# Control_HAT_v0_2B.net
KiCad netlist of a schematic drawn in EAGLE
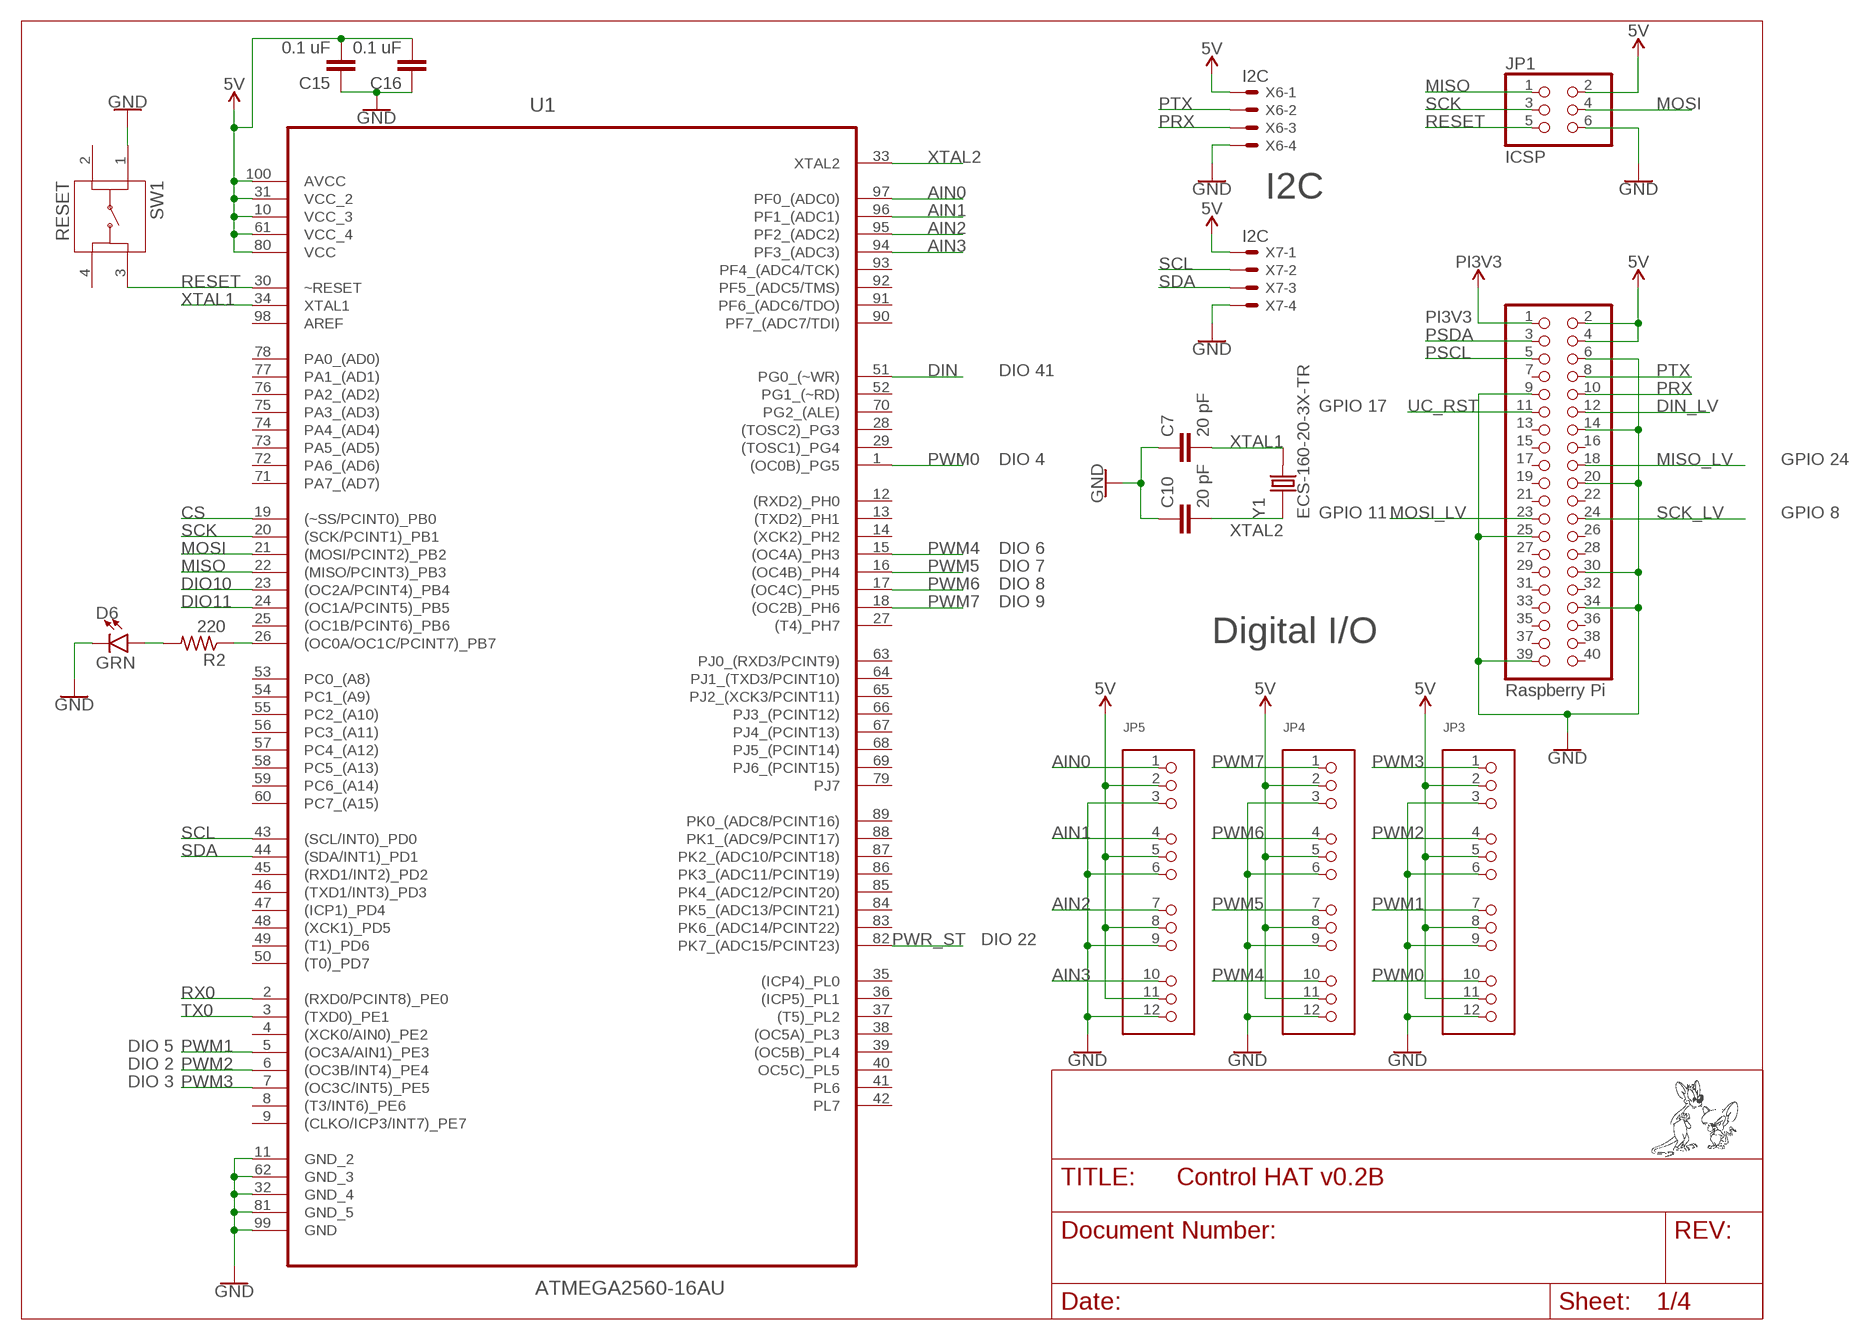
[diagram p0: schematic, sheet 1]
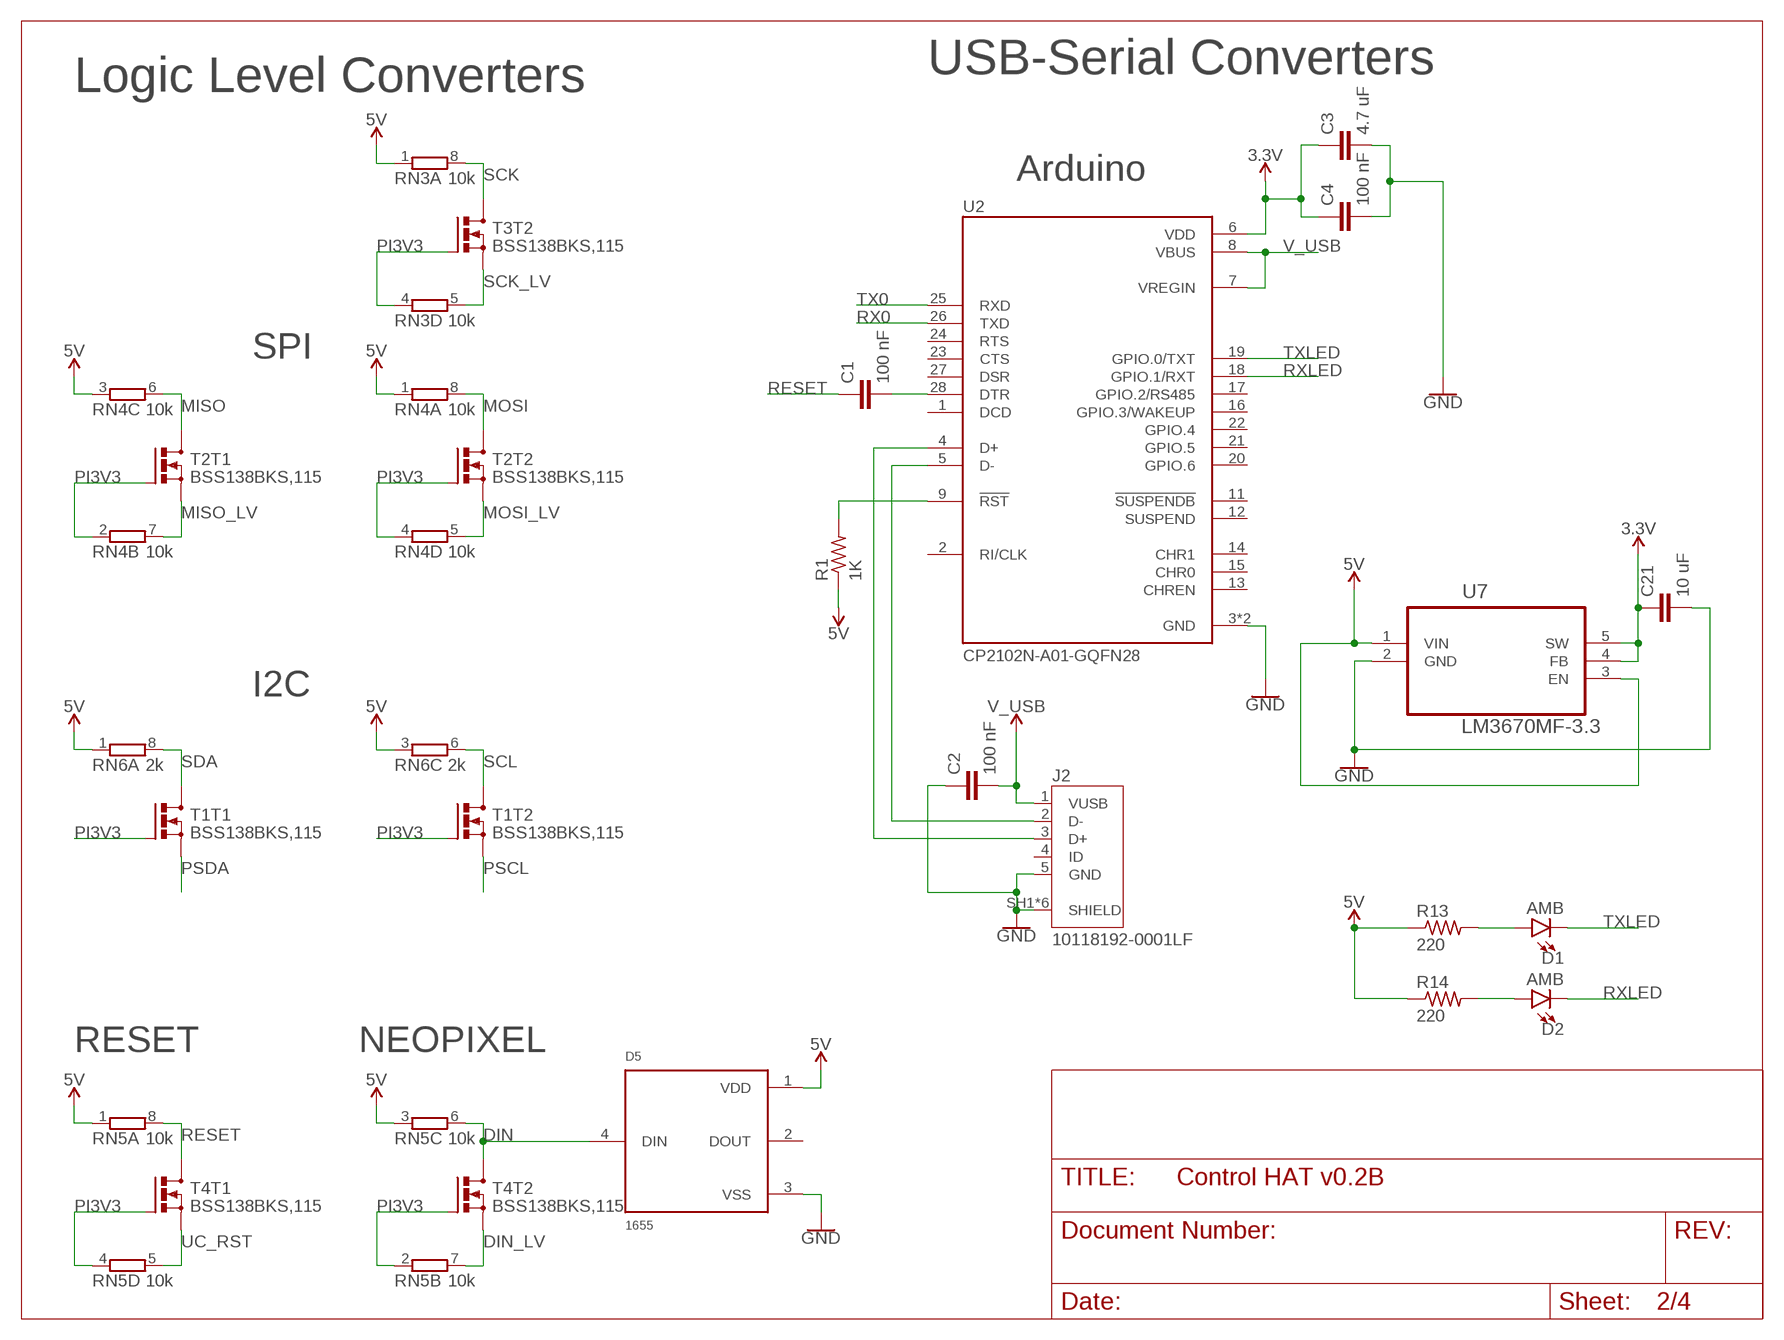
[diagram p1: schematic, sheet 2]
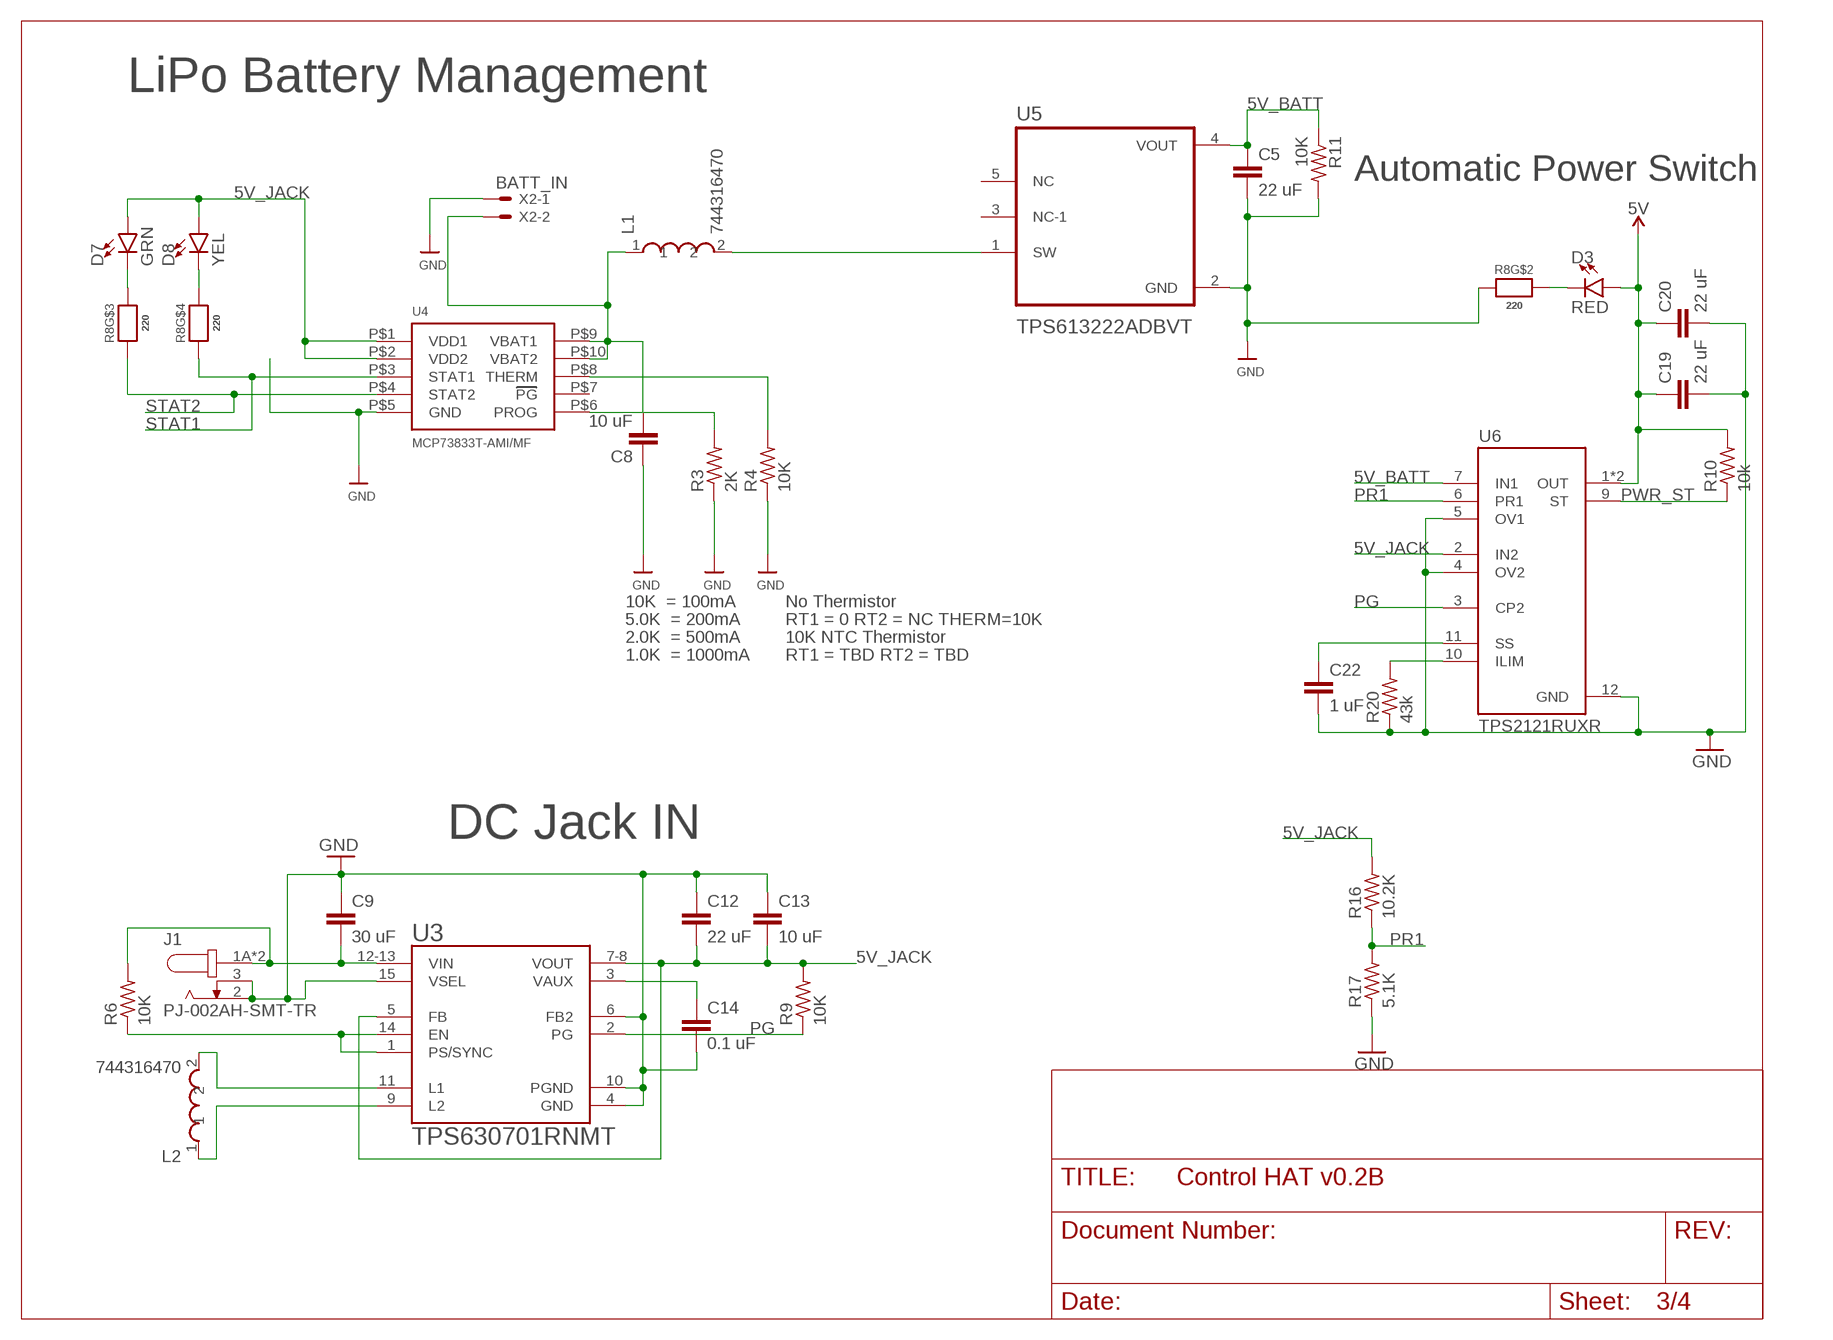
[diagram p2: schematic, sheet 3]
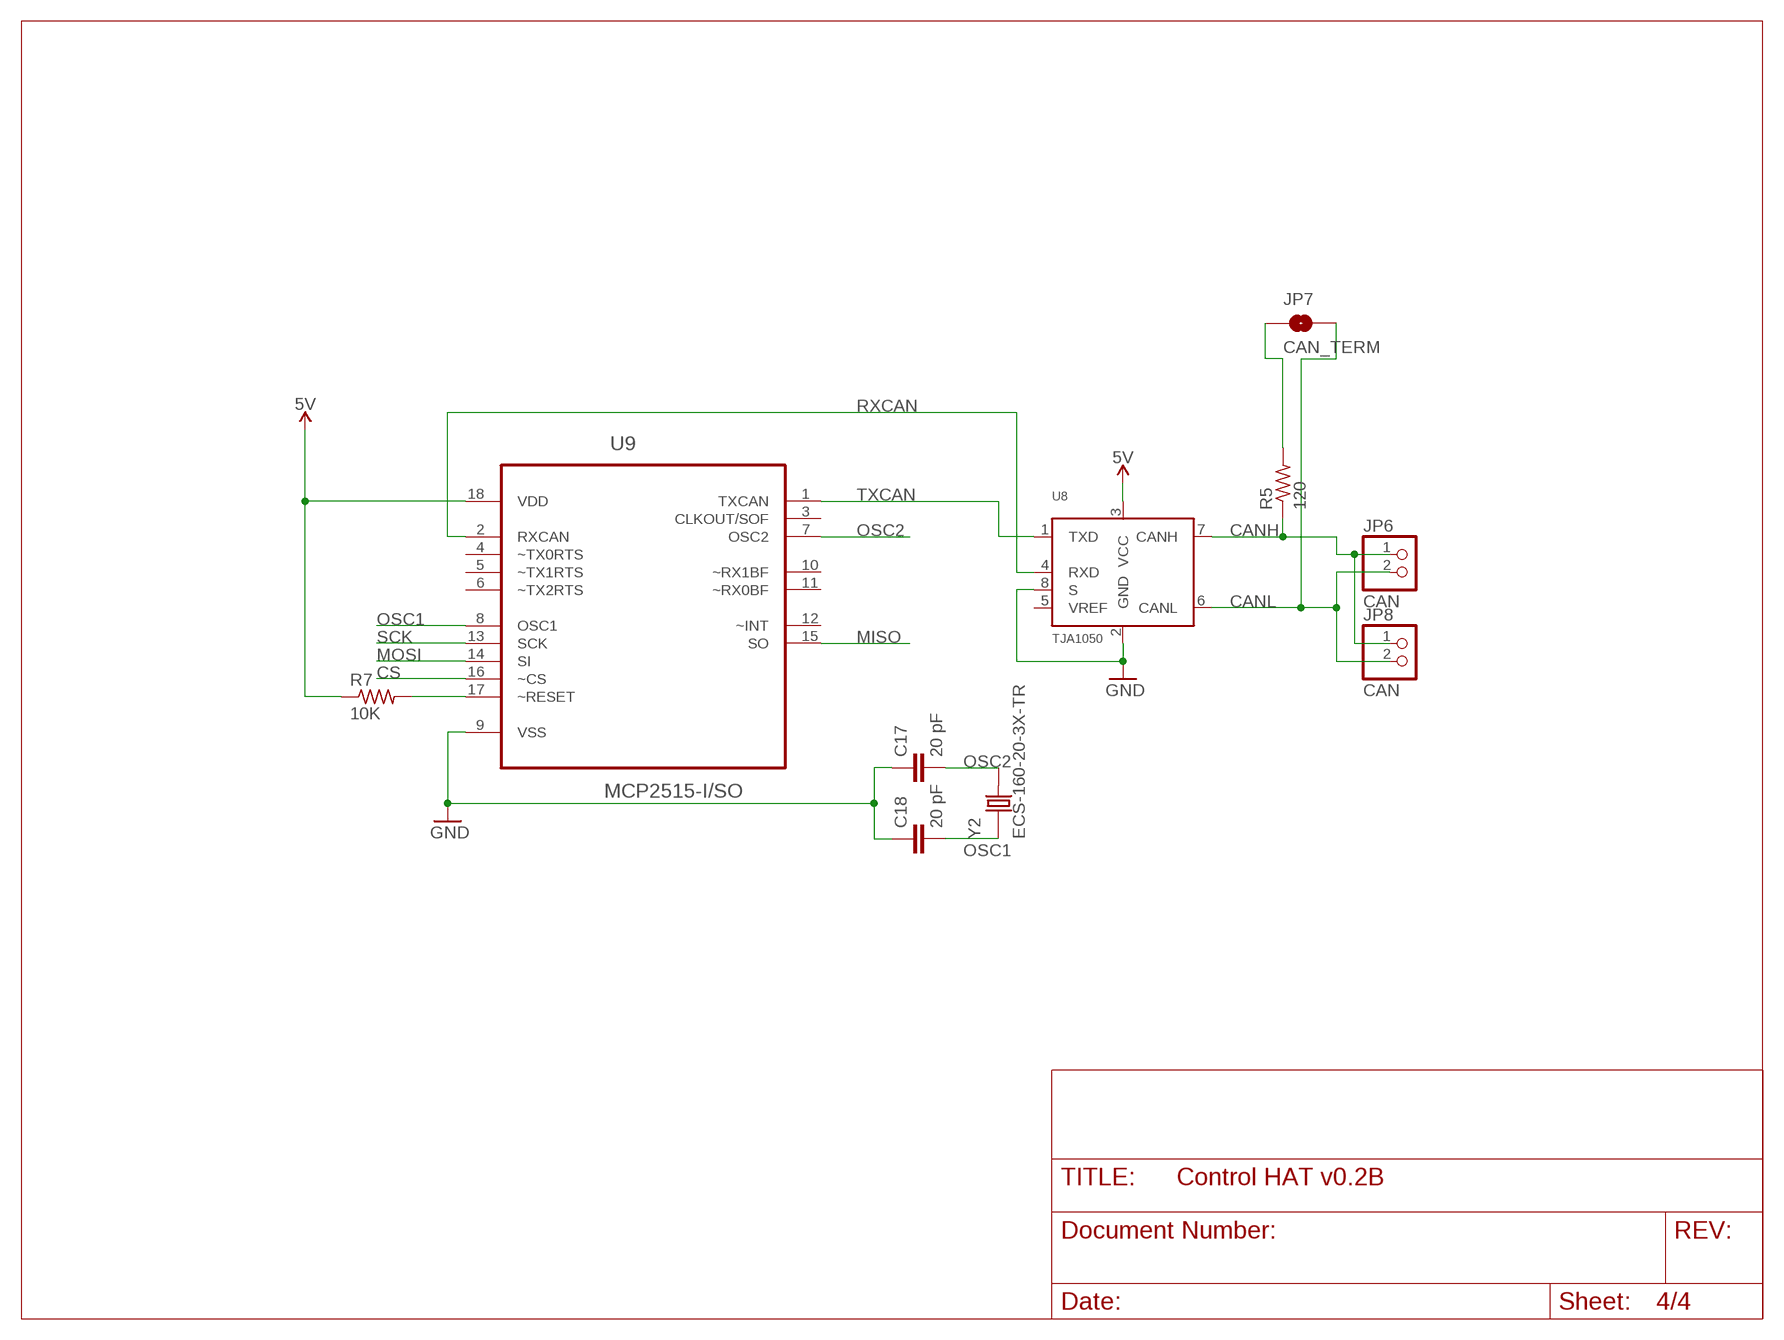
[diagram p3: schematic, sheet 4]

(export (version "E")
  (design (tool "Eeschema 10.0.6"))
  (components
    (comp (ref "C1")
      (value "100 nF")
      (footprint "eagle-import:C0603")
      (libsource (lib "eagle-import") (part "C-EUC0603"))
    )
    (comp (ref "C2")
      (value "100 nF")
      (footprint "eagle-import:C0603")
      (libsource (lib "eagle-import") (part "C-EUC0603"))
    )
    (comp (ref "C3")
      (value "4.7 uF")
      (footprint "eagle-import:C0603")
      (libsource (lib "eagle-import") (part "C-EUC0603"))
    )
    (comp (ref "C4")
      (value "100 nF")
      (footprint "eagle-import:C0603")
      (libsource (lib "eagle-import") (part "C-EUC0603"))
    )
    (comp (ref "C21")
      (value "10 uF")
      (footprint "eagle-import:C0603")
      (libsource (lib "eagle-import") (part "C-EUC0603"))
    )
    (comp (ref "D1")
      (value "AMB")
      (footprint "eagle-import:LED-0603")
      (libsource (lib "eagle-import") (part "LED0603"))
    )
    (comp (ref "D2")
      (value "AMB")
      (footprint "eagle-import:LED-0603")
      (libsource (lib "eagle-import") (part "LED0603"))
    )
    (comp (ref "D5")
      (value "1655")
      (footprint "eagle-import:FCI_1655")
      (fields (field (name "MF") "Adafruit Industries"))
      (libsource (lib "eagle-import") (part "1655"))
    )
    (comp (ref "J2")
      (value "10118192-0001LF")
      (footprint "eagle-import:AMPHENOL_10118192-0001LF")
      (fields (field (name "MF") "Amphenol ICC"))
      (libsource (lib "eagle-import") (part "10118192-0001LF"))
    )
    (comp (ref "R1")
      (value "1K")
      (footprint "eagle-import:R0603")
      (libsource (lib "eagle-import") (part "R-US_R0603"))
    )
    (comp (ref "R13")
      (value "220")
      (footprint "eagle-import:R0603")
      (libsource (lib "eagle-import") (part "R-US_R0603"))
    )
    (comp (ref "R14")
      (value "220")
      (footprint "eagle-import:R0603")
      (libsource (lib "eagle-import") (part "R-US_R0603"))
    )
    (comp (ref "RN3")
      (value "10k")
      (footprint "eagle-import:EXB28V")
      (libsource (lib "eagle-import") (part "4R-NEXB28V"))
    )
    (comp (ref "RN4")
      (value "10k")
      (footprint "eagle-import:EXB28V")
      (libsource (lib "eagle-import") (part "4R-NEXB28V"))
    )
    (comp (ref "RN5")
      (value "10k")
      (footprint "eagle-import:EXB28V")
      (libsource (lib "eagle-import") (part "4R-NEXB28V"))
    )
    (comp (ref "RN6")
      (value "2k")
      (footprint "eagle-import:EXB28V")
      (libsource (lib "eagle-import") (part "4R-NEXB28V"))
    )
    (comp (ref "T1")
      (value "BSS138BKS,115")
      (footprint "eagle-import:SOT363")
      (fields (field (name "MF") "Nexperia USA"))
      (libsource (lib "eagle-import") (part "BSS138BKS,115"))
    )
    (comp (ref "T2")
      (value "BSS138BKS,115")
      (footprint "eagle-import:SOT363")
      (fields (field (name "MF") "Nexperia USA"))
      (libsource (lib "eagle-import") (part "BSS138BKS,115"))
    )
    (comp (ref "T3")
      (value "BSS138BKS,115")
      (footprint "eagle-import:SOT363")
      (fields (field (name "MF") "Nexperia USA"))
      (libsource (lib "eagle-import") (part "BSS138BKS,115"))
    )
    (comp (ref "T4")
      (value "BSS138BKS,115")
      (footprint "eagle-import:SOT363")
      (fields (field (name "MF") "Nexperia USA"))
      (libsource (lib "eagle-import") (part "BSS138BKS,115"))
    )
    (comp (ref "U2")
      (value "CP2102N-A01-GQFN28")
      (footprint "eagle-import:QFN50P500X500X80-29N")
      (fields (field (name "MF") "Silicon Labs"))
      (libsource (lib "eagle-import") (part "CP2102N-A01-GQFN28"))
    )
    (comp (ref "U7")
      (value "LM3670MF-3.3")
      (footprint "eagle-import:SOT95P284X122-5N")
      (fields (field (name "MF") "Texas Instruments") (field (name "MP") "LM3670MF-3.3/NOPB"))
      (libsource (lib "eagle-import") (part "LM3670MF-3.3"))
    )
    (comp (ref "C7")
      (value "20 pF")
      (footprint "eagle-import:C0603")
      (libsource (lib "eagle-import") (part "C-EUC0603"))
    )
    (comp (ref "C10")
      (value "20 pF")
      (footprint "eagle-import:C0603")
      (libsource (lib "eagle-import") (part "C-EUC0603"))
    )
    (comp (ref "C15")
      (value "0.1 uF")
      (footprint "eagle-import:C0603")
      (libsource (lib "eagle-import") (part "C-EUC0603"))
    )
    (comp (ref "C16")
      (value "0.1 uF")
      (footprint "eagle-import:C0603")
      (libsource (lib "eagle-import") (part "C-EUC0603"))
    )
    (comp (ref "D6")
      (value "GRN")
      (footprint "eagle-import:LED-0603")
      (libsource (lib "eagle-import") (part "LED0603"))
    )
    (comp (ref "JP1")
      (value "ICSP")
      (footprint "eagle-import:2X03")
      (libsource (lib "eagle-import") (part "PINHD-2X3"))
    )
    (comp (ref "JP2")
      (value "Raspberry Pi")
      (footprint "eagle-import:2X20")
      (libsource (lib "eagle-import") (part "PINHD-2X20"))
    )
    (comp (ref "JP3")
      (value "HEADER-3X04")
      (footprint "eagle-import:3X04")
      (libsource (lib "eagle-import") (part "HEADER-3X04"))
    )
    (comp (ref "JP4")
      (value "HEADER-3X04")
      (footprint "eagle-import:3X04")
      (libsource (lib "eagle-import") (part "HEADER-3X04"))
    )
    (comp (ref "JP5")
      (value "HEADER-3X04")
      (footprint "eagle-import:3X04")
      (libsource (lib "eagle-import") (part "HEADER-3X04"))
    )
    (comp (ref "R2")
      (value "220")
      (footprint "eagle-import:R0603")
      (libsource (lib "eagle-import") (part "R-US_R0603"))
    )
    (comp (ref "SW1")
      (value "RESET")
      (footprint "eagle-import:SW_1825910-6-4")
      (fields (field (name "COMMENT") "1825910-6") (field (name "MF") "TE Connectivity"))
      (libsource (lib "eagle-import") (part "1825910-6"))
    )
    (comp (ref "U1")
      (value "ATMEGA2560-16AU")
      (footprint "eagle-import:QFP50P1600X1600X120-100N")
      (fields (field (name "MF") "Microchip"))
      (libsource (lib "eagle-import") (part "ATMEGA2560-16AU"))
    )
    (comp (ref "X6")
      (value "I2C")
      (footprint "eagle-import:JST-XH-04-PACKAGE-LONG-PAD")
      (libsource (lib "eagle-import") (part "JST-XH-04-PIN-LONG-PAD"))
    )
    (comp (ref "X7")
      (value "I2C")
      (footprint "eagle-import:JST-XH-04-PACKAGE-LONG-PAD")
      (libsource (lib "eagle-import") (part "JST-XH-04-PIN-LONG-PAD"))
    )
    (comp (ref "Y1")
      (value "ECS-160-20-3X-TR")
      (footprint "eagle-import:XTAL_ECS-160-20-3X-TR")
      (fields (field (name "MF") "ECS Inc."))
      (libsource (lib "eagle-import") (part "ECS-160-20-3X-TR"))
    )
    (comp (ref "C5")
      (value "22 uF")
      (footprint "eagle-import:C0603")
      (libsource (lib "eagle-import") (part "C-EUC0603"))
    )
    (comp (ref "C8")
      (value "10 uF")
      (footprint "eagle-import:C0603")
      (libsource (lib "eagle-import") (part "C-EUC0603"))
    )
    (comp (ref "C9")
      (value "30 uF")
      (footprint "eagle-import:C0603")
      (libsource (lib "eagle-import") (part "C-EUC0603"))
    )
    (comp (ref "C12")
      (value "22 uF")
      (footprint "eagle-import:C0603")
      (libsource (lib "eagle-import") (part "C-EUC0603"))
    )
    (comp (ref "C13")
      (value "10 uF")
      (footprint "eagle-import:C0603")
      (libsource (lib "eagle-import") (part "C-EUC0603"))
    )
    (comp (ref "C14")
      (value "0.1 uF")
      (footprint "eagle-import:C0603")
      (libsource (lib "eagle-import") (part "C-EUC0603"))
    )
    (comp (ref "C19")
      (value "22 uF")
      (footprint "eagle-import:C0603")
      (libsource (lib "eagle-import") (part "C-EUC0603"))
    )
    (comp (ref "C20")
      (value "22 uF")
      (footprint "eagle-import:C0603")
      (libsource (lib "eagle-import") (part "C-EUC0603"))
    )
    (comp (ref "C22")
      (value "1 uF")
      (footprint "eagle-import:C0603")
      (libsource (lib "eagle-import") (part "C-EUC0603"))
    )
    (comp (ref "D3")
      (value "RED")
      (footprint "eagle-import:LED-0603")
      (libsource (lib "eagle-import") (part "LED0603"))
    )
    (comp (ref "D7")
      (value "GRN")
      (footprint "eagle-import:LED-0603")
      (libsource (lib "eagle-import") (part "LED0603"))
    )
    (comp (ref "D8")
      (value "YEL")
      (footprint "eagle-import:LED-0603")
      (libsource (lib "eagle-import") (part "LED0603"))
    )
    (comp (ref "J1")
      (value "PJ-002AH-SMT-TR")
      (footprint "eagle-import:CUI_PJ-002AH-SMT-TR")
      (fields (field (name "DIGI-KEY_PART_NUMBER") "CP-002AHPJCT-ND") (field (name "MF") "CUI Inc."))
      (libsource (lib "eagle-import") (part "PJ-002AH-SMT-TR"))
    )
    (comp (ref "L1")
      (value "744316470")
      (footprint "eagle-import:INDC2220X16")
      (fields (field (name "MF") "Wurth Electronics"))
      (libsource (lib "eagle-import") (part "744316470"))
    )
    (comp (ref "L2")
      (value "744316470")
      (footprint "eagle-import:INDC2220X16")
      (fields (field (name "MF") "Wurth Electronics"))
      (libsource (lib "eagle-import") (part "744316470"))
    )
    (comp (ref "R3")
      (value "2K")
      (footprint "eagle-import:R0603")
      (libsource (lib "eagle-import") (part "R-US_R0603"))
    )
    (comp (ref "R4")
      (value "10K")
      (footprint "eagle-import:R0603")
      (libsource (lib "eagle-import") (part "R-US_R0603"))
    )
    (comp (ref "R6")
      (value "10K")
      (footprint "eagle-import:R0603")
      (libsource (lib "eagle-import") (part "R-US_R0603"))
    )
    (comp (ref "R8")
      (value "220")
      (footprint "eagle-import:RESPACK_4X0603")
      (libsource (lib "eagle-import") (part "RESISTOR_4PACK"))
    )
    (comp (ref "R9")
      (value "10K")
      (footprint "eagle-import:R0603")
      (libsource (lib "eagle-import") (part "R-US_R0603"))
    )
    (comp (ref "R10")
      (value "10k")
      (footprint "eagle-import:R0603")
      (libsource (lib "eagle-import") (part "R-US_R0603"))
    )
    (comp (ref "R11")
      (value "10K")
      (footprint "eagle-import:R0603")
      (libsource (lib "eagle-import") (part "R-US_R0603"))
    )
    (comp (ref "R16")
      (value "10.2K")
      (footprint "eagle-import:R0603")
      (libsource (lib "eagle-import") (part "R-US_R0603"))
    )
    (comp (ref "R17")
      (value "5.1K")
      (footprint "eagle-import:R0603")
      (libsource (lib "eagle-import") (part "R-US_R0603"))
    )
    (comp (ref "R20")
      (value "43k")
      (footprint "eagle-import:R0603")
      (libsource (lib "eagle-import") (part "R-US_R0603"))
    )
    (comp (ref "U3")
      (value "TPS630701RNMT")
      (footprint "eagle-import:QFN50P250X300X100-15N")
      (fields (field (name "MF") "Texas Instruments") (field (name "MP") "TPS63070RNMT"))
      (libsource (lib "eagle-import") (part "TPS63070RNMT"))
    )
    (comp (ref "U4")
      (value "MCP73833T-AMI/MF")
      (footprint "eagle-import:DFN10_3X3MM")
      (libsource (lib "eagle-import") (part "MCP73833DFN"))
    )
    (comp (ref "U5")
      (value "TPS613222ADBVT")
      (footprint "eagle-import:SOT95P280X145-5N")
      (fields (field (name "MF") "Texas Instruments"))
      (libsource (lib "eagle-import") (part "TPS613222ADBVT"))
    )
    (comp (ref "U6")
      (value "TPS2121RUXR")
      (footprint "eagle-import:IC_TPS2121RUXR")
      (fields (field (name "MF") "Texas Instruments"))
      (libsource (lib "eagle-import") (part "TPS2121RUXR"))
    )
    (comp (ref "X2")
      (value "BATT_IN")
      (footprint "eagle-import:JST-XH-02-PACKAGE-LONG-PAD")
      (libsource (lib "eagle-import") (part "JST-XH-02-PIN-LONG-PAD"))
    )
    (comp (ref "C17")
      (value "20 pF")
      (footprint "eagle-import:C0603")
      (libsource (lib "eagle-import") (part "C-EUC0603"))
    )
    (comp (ref "C18")
      (value "20 pF")
      (footprint "eagle-import:C0603")
      (libsource (lib "eagle-import") (part "C-EUC0603"))
    )
    (comp (ref "JP6")
      (value "CAN")
      (footprint "eagle-import:1X02")
      (libsource (lib "eagle-import") (part "PINHD-1X2"))
    )
    (comp (ref "JP7")
      (value "CAN_TERM")
      (footprint "eagle-import:SMT-JUMPER_2_NO_NO-SILK")
      (libsource (lib "eagle-import") (part "JUMPER-SMT_2_NO_NO-SILK"))
    )
    (comp (ref "JP8")
      (value "CAN")
      (footprint "eagle-import:1X02")
      (libsource (lib "eagle-import") (part "PINHD-1X2"))
    )
    (comp (ref "R5")
      (value "120")
      (footprint "eagle-import:R0603")
      (libsource (lib "eagle-import") (part "R-US_R0603"))
    )
    (comp (ref "R7")
      (value "10K")
      (footprint "eagle-import:R0603")
      (libsource (lib "eagle-import") (part "R-US_R0603"))
    )
    (comp (ref "U8")
      (value "TJA1050")
      (footprint "eagle-import:SOT96-1")
      (fields (field (name "DIGI-KEY_PART_NUMBER") "568-10292-1-ND") (field (name "MF") "NXP USA"))
      (libsource (lib "eagle-import") (part "TJA1050"))
    )
    (comp (ref "U9")
      (value "MCP2515-I/SO")
      (footprint "eagle-import:SOIC127P1034X264-18N")
      (fields (field (name "DIGI-KEY_PART_NUMBER") "MCP2515-I/SO-ND") (field (name "MF") "Microchip"))
      (libsource (lib "eagle-import") (part "MCP2515-I/SO"))
    )
    (comp (ref "Y2")
      (value "ECS-160-20-3X-TR")
      (footprint "eagle-import:XTAL_ECS-160-20-3X-TR")
      (fields (field (name "MF") "ECS Inc."))
      (libsource (lib "eagle-import") (part "ECS-160-20-3X-TR"))
    )
  )
  (nets
    (net (code "1") (name "3.3V") (class "Default")
      (node (ref "C21") (pin "1") (pinfunction "1_1") (pintype "passive"))
      (node (ref "C3") (pin "1") (pinfunction "1_1") (pintype "passive"))
      (node (ref "C4") (pin "1") (pinfunction "1_1") (pintype "passive"))
      (node (ref "U2") (pin "6") (pinfunction "VDD_6") (pintype "power_in"))
      (node (ref "U7") (pin "4") (pinfunction "FB_4") (pintype "passive"))
      (node (ref "U7") (pin "5") (pinfunction "SW_5") (pintype "output"))
    )
    (net (code "2") (name "5V") (class "Default")
      (node (ref "C15") (pin "2") (pinfunction "2_2") (pintype "passive"))
      (node (ref "C16") (pin "2") (pinfunction "2_2") (pintype "passive"))
      (node (ref "C19") (pin "1") (pinfunction "1_1") (pintype "passive"))
      (node (ref "C20") (pin "1") (pinfunction "1_1") (pintype "passive"))
      (node (ref "D3") (pin "A") (pinfunction "A_A") (pintype "passive"))
      (node (ref "D5") (pin "1") (pinfunction "VDD_1") (pintype "power_in"))
      (node (ref "JP1") (pin "2") (pinfunction "2_2") (pintype "passive"))
      (node (ref "JP2") (pin "2") (pinfunction "2_2") (pintype "passive"))
      (node (ref "JP2") (pin "4") (pinfunction "4_4") (pintype "passive"))
      (node (ref "JP3") (pin "11") (pinfunction "11_11") (pintype "passive"))
      (node (ref "JP3") (pin "2") (pinfunction "2_2") (pintype "passive"))
      (node (ref "JP3") (pin "5") (pinfunction "5_5") (pintype "passive"))
      (node (ref "JP3") (pin "8") (pinfunction "8_8") (pintype "passive"))
      (node (ref "JP4") (pin "11") (pinfunction "11_11") (pintype "passive"))
      (node (ref "JP4") (pin "2") (pinfunction "2_2") (pintype "passive"))
      (node (ref "JP4") (pin "5") (pinfunction "5_5") (pintype "passive"))
      (node (ref "JP4") (pin "8") (pinfunction "8_8") (pintype "passive"))
      (node (ref "JP5") (pin "11") (pinfunction "11_11") (pintype "passive"))
      (node (ref "JP5") (pin "2") (pinfunction "2_2") (pintype "passive"))
      (node (ref "JP5") (pin "5") (pinfunction "5_5") (pintype "passive"))
      (node (ref "JP5") (pin "8") (pinfunction "8_8") (pintype "passive"))
      (node (ref "R1") (pin "1") (pinfunction "1_1") (pintype "passive"))
      (node (ref "R10") (pin "2") (pinfunction "2_2") (pintype "passive"))
      (node (ref "R13") (pin "1") (pinfunction "1_1") (pintype "passive"))
      (node (ref "R14") (pin "1") (pinfunction "1_1") (pintype "passive"))
      (node (ref "R7") (pin "1") (pinfunction "1_1") (pintype "passive"))
      (node (ref "RN3") (pin "1") (pinfunction "1_1") (pintype "passive"))
      (node (ref "RN4") (pin "1") (pinfunction "1_1") (pintype "passive"))
      (node (ref "RN4") (pin "3") (pinfunction "1_3") (pintype "passive"))
      (node (ref "RN5") (pin "1") (pinfunction "1_1") (pintype "passive"))
      (node (ref "RN5") (pin "3") (pinfunction "1_3") (pintype "passive"))
      (node (ref "RN6") (pin "1") (pinfunction "1_1") (pintype "passive"))
      (node (ref "RN6") (pin "3") (pinfunction "1_3") (pintype "passive"))
      (node (ref "U1") (pin "10") (pinfunction "VCC_3_10") (pintype "power_in"))
      (node (ref "U1") (pin "100") (pinfunction "AVCC_100") (pintype "power_in"))
      (node (ref "U1") (pin "31") (pinfunction "VCC_2_31") (pintype "power_in"))
      (node (ref "U1") (pin "61") (pinfunction "VCC_4_61") (pintype "power_in"))
      (node (ref "U1") (pin "80") (pinfunction "VCC_80") (pintype "power_in"))
      (node (ref "U6") (pin "1") (pinfunction "OUT_1") (pintype "output"))
      (node (ref "U6") (pin "8") (pinfunction "OUT_8") (pintype "output"))
      (node (ref "U7") (pin "1") (pinfunction "VIN_1") (pintype "input"))
      (node (ref "U7") (pin "3") (pinfunction "EN_3") (pintype "passive"))
      (node (ref "U8") (pin "3") (pinfunction "VCC_3") (pintype "bidirectional"))
      (node (ref "U9") (pin "18") (pinfunction "VDD_18") (pintype "power_in"))
      (node (ref "X6") (pin "1") (pinfunction "S_1") (pintype "passive"))
      (node (ref "X7") (pin "1") (pinfunction "S_1") (pintype "passive"))
    )
    (net (code "3") (name "5V_BATT") (class "Default")
      (node (ref "C5") (pin "1") (pinfunction "1_1") (pintype "passive"))
      (node (ref "R11") (pin "1") (pinfunction "1_1") (pintype "passive"))
      (node (ref "U5") (pin "4") (pinfunction "VOUT_4") (pintype "output"))
      (node (ref "U6") (pin "7") (pinfunction "IN1_7") (pintype "input"))
    )
    (net (code "4") (name "5V_JACK") (class "Default")
      (node (ref "C12") (pin "2") (pinfunction "2_2") (pintype "passive"))
      (node (ref "C13") (pin "2") (pinfunction "2_2") (pintype "passive"))
      (node (ref "D7") (pin "A") (pinfunction "A_A") (pintype "passive"))
      (node (ref "D8") (pin "A") (pinfunction "A_A") (pintype "passive"))
      (node (ref "R16") (pin "2") (pinfunction "2_2") (pintype "passive"))
      (node (ref "R9") (pin "2") (pinfunction "2_2") (pintype "passive"))
      (node (ref "U3") (pin "5") (pinfunction "FB_5") (pintype "input"))
      (node (ref "U3") (pin "7-8") (pinfunction "VOUT_7-8") (pintype "output"))
      (node (ref "U4") (pin "P$1") (pinfunction "VDD1_P$1") (pintype "bidirectional"))
      (node (ref "U4") (pin "P$2") (pinfunction "VDD2_P$2") (pintype "bidirectional"))
      (node (ref "U6") (pin "2") (pinfunction "IN2_2") (pintype "input"))
    )
    (net (code "5") (name "AIN0") (class "Default")
      (node (ref "JP5") (pin "1") (pinfunction "1_1") (pintype "passive"))
      (node (ref "U1") (pin "97") (pinfunction "PF0_(ADC0)_97") (pintype "bidirectional"))
    )
    (net (code "6") (name "AIN1") (class "Default")
      (node (ref "JP5") (pin "4") (pinfunction "4_4") (pintype "passive"))
      (node (ref "U1") (pin "96") (pinfunction "PF1_(ADC1)_96") (pintype "bidirectional"))
    )
    (net (code "7") (name "AIN2") (class "Default")
      (node (ref "JP5") (pin "7") (pinfunction "7_7") (pintype "passive"))
      (node (ref "U1") (pin "95") (pinfunction "PF2_(ADC2)_95") (pintype "bidirectional"))
    )
    (net (code "8") (name "AIN3") (class "Default")
      (node (ref "JP5") (pin "10") (pinfunction "10_10") (pintype "passive"))
      (node (ref "U1") (pin "94") (pinfunction "PF3_(ADC3)_94") (pintype "bidirectional"))
    )
    (net (code "9") (name "CANH") (class "Default")
      (node (ref "JP6") (pin "1") (pinfunction "1_1") (pintype "passive"))
      (node (ref "JP8") (pin "1") (pinfunction "1_1") (pintype "passive"))
      (node (ref "R5") (pin "1") (pinfunction "1_1") (pintype "passive"))
      (node (ref "U8") (pin "7") (pinfunction "CANH_7") (pintype "bidirectional"))
    )
    (net (code "10") (name "CANL") (class "Default")
      (node (ref "JP6") (pin "2") (pinfunction "2_2") (pintype "passive"))
      (node (ref "JP7") (pin "2") (pinfunction "2_2") (pintype "passive"))
      (node (ref "JP8") (pin "2") (pinfunction "2_2") (pintype "passive"))
      (node (ref "U8") (pin "6") (pinfunction "CANL_6") (pintype "bidirectional"))
    )
    (net (code "11") (name "CS") (class "Default")
      (node (ref "U1") (pin "19") (pinfunction "(~{SS/PCINT0})_PB0_19") (pintype "bidirectional"))
      (node (ref "U9") (pin "16") (pinfunction "~{CS}_16") (pintype "input"))
    )
    (net (code "12") (name "DIN") (class "Default")
      (node (ref "D5") (pin "4") (pinfunction "DIN_4") (pintype "input"))
      (node (ref "RN5") (pin "6") (pinfunction "2_6") (pintype "passive"))
      (node (ref "T4") (pin "3") (pinfunction "D_3") (pintype "passive"))
      (node (ref "U1") (pin "51") (pinfunction "PG0_(~{WR})_51") (pintype "bidirectional"))
    )
    (net (code "13") (name "DIN_LV") (class "Default")
      (node (ref "JP2") (pin "12") (pinfunction "12_12") (pintype "passive"))
      (node (ref "RN5") (pin "7") (pinfunction "2_7") (pintype "passive"))
      (node (ref "T4") (pin "4") (pinfunction "S_4") (pintype "passive"))
    )
    (net (code "14") (name "DIO10") (class "Default")
      (node (ref "U1") (pin "23") (pinfunction "(OC2A/PCINT4)_PB4_23") (pintype "bidirectional"))
    )
    (net (code "15") (name "DIO11") (class "Default")
      (node (ref "U1") (pin "24") (pinfunction "(OC1A/PCINT5)_PB5_24") (pintype "bidirectional"))
    )
    (net (code "16") (name "GND") (class "Default")
      (node (ref "C10") (pin "1") (pinfunction "1_1") (pintype "passive"))
      (node (ref "C12") (pin "1") (pinfunction "1_1") (pintype "passive"))
      (node (ref "C13") (pin "1") (pinfunction "1_1") (pintype "passive"))
      (node (ref "C14") (pin "2") (pinfunction "2_2") (pintype "passive"))
      (node (ref "C15") (pin "1") (pinfunction "1_1") (pintype "passive"))
      (node (ref "C16") (pin "1") (pinfunction "1_1") (pintype "passive"))
      (node (ref "C17") (pin "1") (pinfunction "1_1") (pintype "passive"))
      (node (ref "C18") (pin "1") (pinfunction "1_1") (pintype "passive"))
      (node (ref "C19") (pin "2") (pinfunction "2_2") (pintype "passive"))
      (node (ref "C2") (pin "1") (pinfunction "1_1") (pintype "passive"))
      (node (ref "C20") (pin "2") (pinfunction "2_2") (pintype "passive"))
      (node (ref "C21") (pin "2") (pinfunction "2_2") (pintype "passive"))
      (node (ref "C22") (pin "2") (pinfunction "2_2") (pintype "passive"))
      (node (ref "C3") (pin "2") (pinfunction "2_2") (pintype "passive"))
      (node (ref "C4") (pin "2") (pinfunction "2_2") (pintype "passive"))
      (node (ref "C5") (pin "2") (pinfunction "2_2") (pintype "passive"))
      (node (ref "C7") (pin "1") (pinfunction "1_1") (pintype "passive"))
      (node (ref "C8") (pin "1") (pinfunction "1_1") (pintype "passive"))
      (node (ref "C9") (pin "1") (pinfunction "1_1") (pintype "passive"))
      (node (ref "D5") (pin "3") (pinfunction "VSS_3") (pintype "passive"))
      (node (ref "D6") (pin "C") (pinfunction "C_C") (pintype "passive"))
      (node (ref "J1") (pin "2") (pinfunction "2_2") (pintype "passive"))
      (node (ref "J1") (pin "3") (pinfunction "3_3") (pintype "passive"))
      (node (ref "J2") (pin "5") (pinfunction "GND_5") (pintype "passive"))
      (node (ref "J2") (pin "SH1") (pinfunction "SHIELD_SH1") (pintype "passive"))
      (node (ref "J2") (pin "SH2") (pinfunction "SHIELD_SH2") (pintype "passive"))
      (node (ref "J2") (pin "SH3") (pinfunction "SHIELD_SH3") (pintype "passive"))
      (node (ref "J2") (pin "SH4") (pinfunction "SHIELD_SH4") (pintype "passive"))
      (node (ref "J2") (pin "SH5") (pinfunction "SHIELD_SH5") (pintype "passive"))
      (node (ref "J2") (pin "SH6") (pinfunction "SHIELD_SH6") (pintype "passive"))
      (node (ref "JP1") (pin "6") (pinfunction "6_6") (pintype "passive"))
      (node (ref "JP2") (pin "14") (pinfunction "14_14") (pintype "passive"))
      (node (ref "JP2") (pin "20") (pinfunction "20_20") (pintype "passive"))
      (node (ref "JP2") (pin "25") (pinfunction "25_25") (pintype "passive"))
      (node (ref "JP2") (pin "30") (pinfunction "30_30") (pintype "passive"))
      (node (ref "JP2") (pin "34") (pinfunction "34_34") (pintype "passive"))
      (node (ref "JP2") (pin "39") (pinfunction "39_39") (pintype "passive"))
      (node (ref "JP2") (pin "6") (pinfunction "6_6") (pintype "passive"))
      (node (ref "JP2") (pin "9") (pinfunction "9_9") (pintype "passive"))
      (node (ref "JP3") (pin "12") (pinfunction "12_12") (pintype "passive"))
      (node (ref "JP3") (pin "3") (pinfunction "3_3") (pintype "passive"))
      (node (ref "JP3") (pin "6") (pinfunction "6_6") (pintype "passive"))
      (node (ref "JP3") (pin "9") (pinfunction "9_9") (pintype "passive"))
      (node (ref "JP4") (pin "12") (pinfunction "12_12") (pintype "passive"))
      (node (ref "JP4") (pin "3") (pinfunction "3_3") (pintype "passive"))
      (node (ref "JP4") (pin "6") (pinfunction "6_6") (pintype "passive"))
      (node (ref "JP4") (pin "9") (pinfunction "9_9") (pintype "passive"))
      (node (ref "JP5") (pin "12") (pinfunction "12_12") (pintype "passive"))
      (node (ref "JP5") (pin "3") (pinfunction "3_3") (pintype "passive"))
      (node (ref "JP5") (pin "6") (pinfunction "6_6") (pintype "passive"))
      (node (ref "JP5") (pin "9") (pinfunction "9_9") (pintype "passive"))
      (node (ref "R11") (pin "2") (pinfunction "2_2") (pintype "passive"))
      (node (ref "R17") (pin "1") (pinfunction "1_1") (pintype "passive"))
      (node (ref "R20") (pin "1") (pinfunction "1_1") (pintype "passive"))
      (node (ref "R3") (pin "1") (pinfunction "1_1") (pintype "passive"))
      (node (ref "R4") (pin "1") (pinfunction "1_1") (pintype "passive"))
      (node (ref "R8") (pin "2") (pinfunction "1_2") (pintype "passive"))
      (node (ref "SW1") (pin "1") (pinfunction "1_1") (pintype "passive"))
      (node (ref "U1") (pin "11") (pinfunction "GND_2_11") (pintype "passive"))
      (node (ref "U1") (pin "32") (pinfunction "GND_4_32") (pintype "passive"))
      (node (ref "U1") (pin "62") (pinfunction "GND_3_62") (pintype "passive"))
      (node (ref "U1") (pin "81") (pinfunction "GND_5_81") (pintype "passive"))
      (node (ref "U1") (pin "99") (pinfunction "GND_99") (pintype "passive"))
      (node (ref "U2") (pin "29") (pinfunction "GND_29") (pintype "power_in"))
      (node (ref "U2") (pin "3") (pinfunction "GND_3") (pintype "power_in"))
      (node (ref "U3") (pin "10") (pinfunction "PGND_10") (pintype "power_in"))
      (node (ref "U3") (pin "15") (pinfunction "VSEL_15") (pintype "input"))
      (node (ref "U3") (pin "4") (pinfunction "GND_4") (pintype "power_in"))
      (node (ref "U3") (pin "6") (pinfunction "FB2_6") (pintype "output"))
      (node (ref "U4") (pin "P$5") (pinfunction "GND_P$5") (pintype "bidirectional"))
      (node (ref "U5") (pin "2") (pinfunction "GND_2") (pintype "power_in"))
      (node (ref "U6") (pin "12") (pinfunction "GND_12") (pintype "power_in"))
      (node (ref "U6") (pin "4") (pinfunction "OV2_4") (pintype "input"))
      (node (ref "U6") (pin "5") (pinfunction "OV1_5") (pintype "input"))
      (node (ref "U7") (pin "2") (pinfunction "GND_2") (pintype "passive"))
      (node (ref "U8") (pin "2") (pinfunction "GND_2") (pintype "bidirectional"))
      (node (ref "U8") (pin "8") (pinfunction "S_8") (pintype "power_in"))
      (node (ref "U9") (pin "9") (pinfunction "VSS_9") (pintype "power_in"))
      (node (ref "X2") (pin "1") (pinfunction "S_1") (pintype "passive"))
      (node (ref "X6") (pin "4") (pinfunction "S_4") (pintype "passive"))
      (node (ref "X7") (pin "4") (pinfunction "S_4") (pintype "passive"))
    )
    (net (code "17") (name "MISO") (class "Default")
      (node (ref "JP1") (pin "1") (pinfunction "1_1") (pintype "passive"))
      (node (ref "RN4") (pin "6") (pinfunction "2_6") (pintype "passive"))
      (node (ref "T2") (pin "6") (pinfunction "D_6") (pintype "passive"))
      (node (ref "U1") (pin "22") (pinfunction "(MISO/PCINT3)_PB3_22") (pintype "bidirectional"))
      (node (ref "U9") (pin "15") (pinfunction "SO_15") (pintype "output"))
    )
    (net (code "18") (name "MISO_LV") (class "Default")
      (node (ref "JP2") (pin "18") (pinfunction "18_18") (pintype "passive"))
      (node (ref "RN4") (pin "7") (pinfunction "2_7") (pintype "passive"))
      (node (ref "T2") (pin "1") (pinfunction "S_1") (pintype "passive"))
    )
    (net (code "19") (name "MOSI") (class "Default")
      (node (ref "JP1") (pin "4") (pinfunction "4_4") (pintype "passive"))
      (node (ref "RN4") (pin "8") (pinfunction "2_8") (pintype "passive"))
      (node (ref "T2") (pin "3") (pinfunction "D_3") (pintype "passive"))
      (node (ref "U1") (pin "21") (pinfunction "(MOSI/PCINT2)_PB2_21") (pintype "bidirectional"))
      (node (ref "U9") (pin "14") (pinfunction "SI_14") (pintype "input"))
    )
    (net (code "20") (name "MOSI_LV") (class "Default")
      (node (ref "JP2") (pin "23") (pinfunction "23_23") (pintype "passive"))
      (node (ref "RN4") (pin "5") (pinfunction "2_5") (pintype "passive"))
      (node (ref "T2") (pin "4") (pinfunction "S_4") (pintype "passive"))
    )
    (net (code "21") (name "Net-(D1-PadA)") (class "Default")
      (node (ref "D1") (pin "A") (pinfunction "A_A") (pintype "passive"))
      (node (ref "R13") (pin "2") (pinfunction "2_2") (pintype "passive"))
    )
    (net (code "22") (name "Net-(D2-PadA)") (class "Default")
      (node (ref "D2") (pin "A") (pinfunction "A_A") (pintype "passive"))
      (node (ref "R14") (pin "2") (pinfunction "2_2") (pintype "passive"))
    )
    (net (code "23") (name "Net-(D6-PadA)") (class "Default")
      (node (ref "D6") (pin "A") (pinfunction "A_A") (pintype "passive"))
      (node (ref "R2") (pin "2") (pinfunction "2_2") (pintype "passive"))
    )
    (net (code "24") (name "Net-(J2-D+)") (class "Default")
      (node (ref "J2") (pin "3") (pinfunction "D+_3") (pintype "passive"))
      (node (ref "U2") (pin "4") (pinfunction "D+_4") (pintype "bidirectional"))
    )
    (net (code "25") (name "Net-(J2-D-)") (class "Default")
      (node (ref "J2") (pin "2") (pinfunction "D-_2") (pintype "passive"))
      (node (ref "U2") (pin "5") (pinfunction "D-_5") (pintype "bidirectional"))
    )
    (net (code "26") (name "Net-(JP7-Pad1)") (class "Default")
      (node (ref "JP7") (pin "1") (pinfunction "1_1") (pintype "passive"))
      (node (ref "R5") (pin "2") (pinfunction "2_2") (pintype "passive"))
    )
    (net (code "27") (name "Net-(R8B-2)") (class "Default")
      (node (ref "D3") (pin "C") (pinfunction "C_C") (pintype "passive"))
      (node (ref "R8") (pin "7") (pinfunction "2_7") (pintype "passive"))
    )
    (net (code "28") (name "Net-(R8C-2)") (class "Default")
      (node (ref "D7") (pin "C") (pinfunction "C_C") (pintype "passive"))
      (node (ref "R8") (pin "6") (pinfunction "2_6") (pintype "passive"))
    )
    (net (code "29") (name "Net-(R8D-2)") (class "Default")
      (node (ref "D8") (pin "C") (pinfunction "C_C") (pintype "passive"))
      (node (ref "R8") (pin "5") (pinfunction "2_5") (pintype "passive"))
    )
    (net (code "30") (name "Net-(U1-(OC0A{slash}OC1C{slash}PCINT7)_PB7)") (class "Default")
      (node (ref "R2") (pin "1") (pinfunction "1_1") (pintype "passive"))
      (node (ref "U1") (pin "26") (pinfunction "(OC0A/OC1C/PCINT7)_PB7_26") (pintype "bidirectional"))
    )
    (net (code "31") (name "Net-(U2-DTR)") (class "Default")
      (node (ref "C1") (pin "2") (pinfunction "2_2") (pintype "passive"))
      (node (ref "U2") (pin "28") (pinfunction "DTR_28") (pintype "output"))
    )
    (net (code "32") (name "Net-(U2-~{RST})") (class "Default")
      (node (ref "R1") (pin "2") (pinfunction "2_2") (pintype "passive"))
      (node (ref "U2") (pin "9") (pinfunction "~{RST}_9") (pintype "input"))
    )
    (net (code "33") (name "Net-(U3-EN)") (class "Default")
      (node (ref "R6") (pin "1") (pinfunction "1_1") (pintype "passive"))
      (node (ref "U3") (pin "1") (pinfunction "PS/SYNC_1") (pintype "input"))
      (node (ref "U3") (pin "14") (pinfunction "EN_14") (pintype "input"))
    )
    (net (code "34") (name "Net-(U3-L1)") (class "Default")
      (node (ref "L2") (pin "2") (pinfunction "2_2") (pintype "passive"))
      (node (ref "U3") (pin "11") (pinfunction "L1_11") (pintype "input"))
    )
    (net (code "35") (name "Net-(U3-L2)") (class "Default")
      (node (ref "L2") (pin "1") (pinfunction "1_1") (pintype "passive"))
      (node (ref "U3") (pin "9") (pinfunction "L2_9") (pintype "input"))
    )
    (net (code "36") (name "Net-(U3-VAUX)") (class "Default")
      (node (ref "C14") (pin "1") (pinfunction "1_1") (pintype "passive"))
      (node (ref "U3") (pin "3") (pinfunction "VAUX_3") (pintype "output"))
    )
    (net (code "37") (name "Net-(U3-VIN)") (class "Default")
      (node (ref "C9") (pin "2") (pinfunction "2_2") (pintype "passive"))
      (node (ref "J1") (pin "1A") (pinfunction "1_1A") (pintype "passive"))
      (node (ref "J1") (pin "1B") (pinfunction "1_1B") (pintype "passive"))
      (node (ref "R6") (pin "2") (pinfunction "2_2") (pintype "passive"))
      (node (ref "U3") (pin "12-13") (pinfunction "VIN_12-13") (pintype "input"))
    )
    (net (code "38") (name "Net-(U4-PROG)") (class "Default")
      (node (ref "R3") (pin "2") (pinfunction "2_2") (pintype "passive"))
      (node (ref "U4") (pin "P$6") (pinfunction "PROG_P$6") (pintype "bidirectional"))
    )
    (net (code "39") (name "Net-(U4-THERM)") (class "Default")
      (node (ref "R4") (pin "2") (pinfunction "2_2") (pintype "passive"))
      (node (ref "U4") (pin "P$8") (pinfunction "THERM_P$8") (pintype "bidirectional"))
    )
    (net (code "40") (name "Net-(U4-VBAT1)") (class "Default")
      (node (ref "C8") (pin "2") (pinfunction "2_2") (pintype "passive"))
      (node (ref "L1") (pin "1") (pinfunction "1_1") (pintype "passive"))
      (node (ref "U4") (pin "P$10") (pinfunction "VBAT2_P$10") (pintype "bidirectional"))
      (node (ref "U4") (pin "P$9") (pinfunction "VBAT1_P$9") (pintype "bidirectional"))
      (node (ref "X2") (pin "2") (pinfunction "S_2") (pintype "passive"))
    )
    (net (code "41") (name "Net-(U5-SW)") (class "Default")
      (node (ref "L1") (pin "2") (pinfunction "2_2") (pintype "passive"))
      (node (ref "U5") (pin "1") (pinfunction "SW_1") (pintype "bidirectional"))
    )
    (net (code "42") (name "Net-(U6-ILIM)") (class "Default")
      (node (ref "R20") (pin "2") (pinfunction "2_2") (pintype "passive"))
      (node (ref "U6") (pin "10") (pinfunction "ILIM_10") (pintype "passive"))
    )
    (net (code "43") (name "Net-(U6-SS)") (class "Default")
      (node (ref "C22") (pin "1") (pinfunction "1_1") (pintype "passive"))
      (node (ref "U6") (pin "11") (pinfunction "SS_11") (pintype "passive"))
    )
    (net (code "44") (name "Net-(U9-~{RESET})") (class "Default")
      (node (ref "R7") (pin "2") (pinfunction "2_2") (pintype "passive"))
      (node (ref "U9") (pin "17") (pinfunction "~{RESET}_17") (pintype "input"))
    )
    (net (code "45") (name "OSC1") (class "Default")
      (node (ref "C18") (pin "2") (pinfunction "2_2") (pintype "passive"))
      (node (ref "U9") (pin "8") (pinfunction "OSC1_8") (pintype "input"))
      (node (ref "Y2") (pin "1") (pinfunction "1_1") (pintype "passive"))
    )
    (net (code "46") (name "OSC2") (class "Default")
      (node (ref "C17") (pin "2") (pinfunction "2_2") (pintype "passive"))
      (node (ref "U9") (pin "7") (pinfunction "OSC2_7") (pintype "output"))
      (node (ref "Y2") (pin "2") (pinfunction "2_2") (pintype "passive"))
    )
    (net (code "47") (name "PG") (class "Default")
      (node (ref "R9") (pin "1") (pinfunction "1_1") (pintype "passive"))
      (node (ref "U3") (pin "2") (pinfunction "PG_2") (pintype "output"))
      (node (ref "U6") (pin "3") (pinfunction "CP2_3") (pintype "input"))
    )
    (net (code "48") (name "PI3V3") (class "Default")
      (node (ref "JP2") (pin "1") (pinfunction "1_1") (pintype "passive"))
      (node (ref "RN3") (pin "4") (pinfunction "1_4") (pintype "passive"))
      (node (ref "RN4") (pin "2") (pinfunction "1_2") (pintype "passive"))
      (node (ref "RN4") (pin "4") (pinfunction "1_4") (pintype "passive"))
      (node (ref "RN5") (pin "2") (pinfunction "1_2") (pintype "passive"))
      (node (ref "RN5") (pin "4") (pinfunction "1_4") (pintype "passive"))
      (node (ref "T1") (pin "2") (pinfunction "G_2") (pintype "passive"))
      (node (ref "T1") (pin "5") (pinfunction "G_5") (pintype "passive"))
      (node (ref "T2") (pin "2") (pinfunction "G_2") (pintype "passive"))
      (node (ref "T2") (pin "5") (pinfunction "G_5") (pintype "passive"))
      (node (ref "T3") (pin "5") (pinfunction "G_5") (pintype "passive"))
      (node (ref "T4") (pin "2") (pinfunction "G_2") (pintype "passive"))
      (node (ref "T4") (pin "5") (pinfunction "G_5") (pintype "passive"))
    )
    (net (code "49") (name "PR1") (class "Default")
      (node (ref "R16") (pin "1") (pinfunction "1_1") (pintype "passive"))
      (node (ref "R17") (pin "2") (pinfunction "2_2") (pintype "passive"))
      (node (ref "U6") (pin "6") (pinfunction "PR1_6") (pintype "input"))
    )
    (net (code "50") (name "PRX") (class "Default")
      (node (ref "JP2") (pin "10") (pinfunction "10_10") (pintype "passive"))
      (node (ref "X6") (pin "3") (pinfunction "S_3") (pintype "passive"))
    )
    (net (code "51") (name "PSCL") (class "Default")
      (node (ref "JP2") (pin "5") (pinfunction "5_5") (pintype "passive"))
      (node (ref "T1") (pin "4") (pinfunction "S_4") (pintype "passive"))
    )
    (net (code "52") (name "PSDA") (class "Default")
      (node (ref "JP2") (pin "3") (pinfunction "3_3") (pintype "passive"))
      (node (ref "T1") (pin "1") (pinfunction "S_1") (pintype "passive"))
    )
    (net (code "53") (name "PTX") (class "Default")
      (node (ref "JP2") (pin "8") (pinfunction "8_8") (pintype "passive"))
      (node (ref "X6") (pin "2") (pinfunction "S_2") (pintype "passive"))
    )
    (net (code "54") (name "PWM0") (class "Default")
      (node (ref "JP3") (pin "10") (pinfunction "10_10") (pintype "passive"))
      (node (ref "U1") (pin "1") (pinfunction "(OC0B)_PG5_1") (pintype "bidirectional"))
    )
    (net (code "55") (name "PWM1") (class "Default")
      (node (ref "JP3") (pin "7") (pinfunction "7_7") (pintype "passive"))
      (node (ref "U1") (pin "5") (pinfunction "(OC3A/AIN1)_PE3_5") (pintype "bidirectional"))
    )
    (net (code "56") (name "PWM2") (class "Default")
      (node (ref "JP3") (pin "4") (pinfunction "4_4") (pintype "passive"))
      (node (ref "U1") (pin "6") (pinfunction "(OC3B/INT4)_PE4_6") (pintype "bidirectional"))
    )
    (net (code "57") (name "PWM3") (class "Default")
      (node (ref "JP3") (pin "1") (pinfunction "1_1") (pintype "passive"))
      (node (ref "U1") (pin "7") (pinfunction "(OC3C/INT5)_PE5_7") (pintype "bidirectional"))
    )
    (net (code "58") (name "PWM4") (class "Default")
      (node (ref "JP4") (pin "10") (pinfunction "10_10") (pintype "passive"))
      (node (ref "U1") (pin "15") (pinfunction "(OC4A)_PH3_15") (pintype "bidirectional"))
    )
    (net (code "59") (name "PWM5") (class "Default")
      (node (ref "JP4") (pin "7") (pinfunction "7_7") (pintype "passive"))
      (node (ref "U1") (pin "16") (pinfunction "(OC4B)_PH4_16") (pintype "bidirectional"))
    )
    (net (code "60") (name "PWM6") (class "Default")
      (node (ref "JP4") (pin "4") (pinfunction "4_4") (pintype "passive"))
      (node (ref "U1") (pin "17") (pinfunction "(OC4C)_PH5_17") (pintype "bidirectional"))
    )
    (net (code "61") (name "PWM7") (class "Default")
      (node (ref "JP4") (pin "1") (pinfunction "1_1") (pintype "passive"))
      (node (ref "U1") (pin "18") (pinfunction "(OC2B)_PH6_18") (pintype "bidirectional"))
    )
    (net (code "62") (name "PWR_ST") (class "Default")
      (node (ref "R10") (pin "1") (pinfunction "1_1") (pintype "passive"))
      (node (ref "U1") (pin "82") (pinfunction "PK7_(ADC15/PCINT23)_82") (pintype "bidirectional"))
      (node (ref "U6") (pin "9") (pinfunction "ST_9") (pintype "output"))
    )
    (net (code "63") (name "RESET") (class "Default")
      (node (ref "C1") (pin "1") (pinfunction "1_1") (pintype "passive"))
      (node (ref "JP1") (pin "5") (pinfunction "5_5") (pintype "passive"))
      (node (ref "RN5") (pin "8") (pinfunction "2_8") (pintype "passive"))
      (node (ref "SW1") (pin "3") (pinfunction "3_3") (pintype "passive"))
      (node (ref "T4") (pin "6") (pinfunction "D_6") (pintype "passive"))
      (node (ref "U1") (pin "30") (pinfunction "~{RESET}_30") (pintype "input"))
    )
    (net (code "64") (name "RX0") (class "Default")
      (node (ref "U1") (pin "2") (pinfunction "(RXD0/PCINT8)_PE0_2") (pintype "bidirectional"))
      (node (ref "U2") (pin "26") (pinfunction "TXD_26") (pintype "output"))
    )
    (net (code "65") (name "RXCAN") (class "Default")
      (node (ref "U8") (pin "4") (pinfunction "RXD_4") (pintype "bidirectional"))
      (node (ref "U9") (pin "2") (pinfunction "RXCAN_2") (pintype "input"))
    )
    (net (code "66") (name "RXLED") (class "Default")
      (node (ref "D2") (pin "C") (pinfunction "C_C") (pintype "passive"))
      (node (ref "U2") (pin "18") (pinfunction "GPIO.1/RXT_18") (pintype "bidirectional"))
    )
    (net (code "67") (name "SCK") (class "Default")
      (node (ref "JP1") (pin "3") (pinfunction "3_3") (pintype "passive"))
      (node (ref "RN3") (pin "8") (pinfunction "2_8") (pintype "passive"))
      (node (ref "T3") (pin "3") (pinfunction "D_3") (pintype "passive"))
      (node (ref "U1") (pin "20") (pinfunction "(SCK/PCINT1)_PB1_20") (pintype "bidirectional"))
      (node (ref "U9") (pin "13") (pinfunction "SCK_13") (pintype "input"))
    )
    (net (code "68") (name "SCK_LV") (class "Default")
      (node (ref "JP2") (pin "24") (pinfunction "24_24") (pintype "passive"))
      (node (ref "RN3") (pin "5") (pinfunction "2_5") (pintype "passive"))
      (node (ref "T3") (pin "4") (pinfunction "S_4") (pintype "passive"))
    )
    (net (code "69") (name "SCL") (class "Default")
      (node (ref "RN6") (pin "6") (pinfunction "2_6") (pintype "passive"))
      (node (ref "T1") (pin "3") (pinfunction "D_3") (pintype "passive"))
      (node (ref "U1") (pin "43") (pinfunction "(SCL/INT0)_PD0_43") (pintype "bidirectional"))
      (node (ref "X7") (pin "2") (pinfunction "S_2") (pintype "passive"))
    )
    (net (code "70") (name "SDA") (class "Default")
      (node (ref "RN6") (pin "8") (pinfunction "2_8") (pintype "passive"))
      (node (ref "T1") (pin "6") (pinfunction "D_6") (pintype "passive"))
      (node (ref "U1") (pin "44") (pinfunction "(SDA/INT1)_PD1_44") (pintype "bidirectional"))
      (node (ref "X7") (pin "3") (pinfunction "S_3") (pintype "passive"))
    )
    (net (code "71") (name "STAT1") (class "Default")
      (node (ref "R8") (pin "4") (pinfunction "1_4") (pintype "passive"))
      (node (ref "U4") (pin "P$3") (pinfunction "STAT1_P$3") (pintype "bidirectional"))
    )
    (net (code "72") (name "STAT2") (class "Default")
      (node (ref "R8") (pin "3") (pinfunction "1_3") (pintype "passive"))
      (node (ref "U4") (pin "P$4") (pinfunction "STAT2_P$4") (pintype "bidirectional"))
    )
    (net (code "73") (name "TX0") (class "Default")
      (node (ref "U1") (pin "3") (pinfunction "(TXD0)_PE1_3") (pintype "bidirectional"))
      (node (ref "U2") (pin "25") (pinfunction "RXD_25") (pintype "input"))
    )
    (net (code "74") (name "TXCAN") (class "Default")
      (node (ref "U8") (pin "1") (pinfunction "TXD_1") (pintype "output"))
      (node (ref "U9") (pin "1") (pinfunction "TXCAN_1") (pintype "output"))
    )
    (net (code "75") (name "TXLED") (class "Default")
      (node (ref "D1") (pin "C") (pinfunction "C_C") (pintype "passive"))
      (node (ref "U2") (pin "19") (pinfunction "GPIO.0/TXT_19") (pintype "bidirectional"))
    )
    (net (code "76") (name "UC_RST") (class "Default")
      (node (ref "JP2") (pin "11") (pinfunction "11_11") (pintype "passive"))
      (node (ref "RN5") (pin "5") (pinfunction "2_5") (pintype "passive"))
      (node (ref "T4") (pin "1") (pinfunction "S_1") (pintype "passive"))
    )
    (net (code "77") (name "V_USB") (class "Default")
      (node (ref "C2") (pin "2") (pinfunction "2_2") (pintype "passive"))
      (node (ref "J2") (pin "1") (pinfunction "VUSB_1") (pintype "passive"))
      (node (ref "U2") (pin "7") (pinfunction "VREGIN_7") (pintype "power_in"))
      (node (ref "U2") (pin "8") (pinfunction "VBUS_8") (pintype "power_in"))
    )
    (net (code "78") (name "XTAL1") (class "Default")
      (node (ref "C7") (pin "2") (pinfunction "2_2") (pintype "passive"))
      (node (ref "U1") (pin "34") (pinfunction "XTAL1_34") (pintype "input"))
      (node (ref "Y1") (pin "2") (pinfunction "2_2") (pintype "passive"))
    )
    (net (code "79") (name "XTAL2") (class "Default")
      (node (ref "C10") (pin "2") (pinfunction "2_2") (pintype "passive"))
      (node (ref "U1") (pin "33") (pinfunction "XTAL2_33") (pintype "output"))
      (node (ref "Y1") (pin "1") (pinfunction "1_1") (pintype "passive"))
    )
    (net (code "80") (name "unconnected-(D5-DOUT-Pad2)") (class "Default")
      (node (ref "D5") (pin "2") (pinfunction "DOUT_2") (pintype "output"))
    )
    (net (code "81") (name "unconnected-(J2-ID-Pad4)") (class "Default")
      (node (ref "J2") (pin "4") (pinfunction "ID_4") (pintype "passive"))
    )
    (net (code "82") (name "unconnected-(JP2-Pad7)") (class "Default")
      (node (ref "JP2") (pin "7") (pinfunction "7_7") (pintype "passive"))
    )
    (net (code "83") (name "unconnected-(JP2-Pad13)") (class "Default")
      (node (ref "JP2") (pin "13") (pinfunction "13_13") (pintype "passive"))
    )
    (net (code "84") (name "unconnected-(JP2-Pad15)") (class "Default")
      (node (ref "JP2") (pin "15") (pinfunction "15_15") (pintype "passive"))
    )
    (net (code "85") (name "unconnected-(JP2-Pad16)") (class "Default")
      (node (ref "JP2") (pin "16") (pinfunction "16_16") (pintype "passive"))
    )
    (net (code "86") (name "unconnected-(JP2-Pad17)") (class "Default")
      (node (ref "JP2") (pin "17") (pinfunction "17_17") (pintype "passive"))
    )
    (net (code "87") (name "unconnected-(JP2-Pad19)") (class "Default")
      (node (ref "JP2") (pin "19") (pinfunction "19_19") (pintype "passive"))
    )
    (net (code "88") (name "unconnected-(JP2-Pad21)") (class "Default")
      (node (ref "JP2") (pin "21") (pinfunction "21_21") (pintype "passive"))
    )
    (net (code "89") (name "unconnected-(JP2-Pad22)") (class "Default")
      (node (ref "JP2") (pin "22") (pinfunction "22_22") (pintype "passive"))
    )
    (net (code "90") (name "unconnected-(JP2-Pad26)") (class "Default")
      (node (ref "JP2") (pin "26") (pinfunction "26_26") (pintype "passive"))
    )
    (net (code "91") (name "unconnected-(JP2-Pad27)") (class "Default")
      (node (ref "JP2") (pin "27") (pinfunction "27_27") (pintype "passive"))
    )
    (net (code "92") (name "unconnected-(JP2-Pad28)") (class "Default")
      (node (ref "JP2") (pin "28") (pinfunction "28_28") (pintype "passive"))
    )
    (net (code "93") (name "unconnected-(JP2-Pad29)") (class "Default")
      (node (ref "JP2") (pin "29") (pinfunction "29_29") (pintype "passive"))
    )
    (net (code "94") (name "unconnected-(JP2-Pad31)") (class "Default")
      (node (ref "JP2") (pin "31") (pinfunction "31_31") (pintype "passive"))
    )
    (net (code "95") (name "unconnected-(JP2-Pad32)") (class "Default")
      (node (ref "JP2") (pin "32") (pinfunction "32_32") (pintype "passive"))
    )
    (net (code "96") (name "unconnected-(JP2-Pad33)") (class "Default")
      (node (ref "JP2") (pin "33") (pinfunction "33_33") (pintype "passive"))
    )
    (net (code "97") (name "unconnected-(JP2-Pad35)") (class "Default")
      (node (ref "JP2") (pin "35") (pinfunction "35_35") (pintype "passive"))
    )
    (net (code "98") (name "unconnected-(JP2-Pad36)") (class "Default")
      (node (ref "JP2") (pin "36") (pinfunction "36_36") (pintype "passive"))
    )
    (net (code "99") (name "unconnected-(JP2-Pad37)") (class "Default")
      (node (ref "JP2") (pin "37") (pinfunction "37_37") (pintype "passive"))
    )
    (net (code "100") (name "unconnected-(JP2-Pad38)") (class "Default")
      (node (ref "JP2") (pin "38") (pinfunction "38_38") (pintype "passive"))
    )
    (net (code "101") (name "unconnected-(JP2-Pad40)") (class "Default")
      (node (ref "JP2") (pin "40") (pinfunction "40_40") (pintype "passive"))
    )
    (net (code "102") (name "unconnected-(SW1-Pad2)") (class "Default")
      (node (ref "SW1") (pin "2") (pinfunction "2_2") (pintype "passive"))
    )
    (net (code "103") (name "unconnected-(SW1-Pad4)") (class "Default")
      (node (ref "SW1") (pin "4") (pinfunction "4_4") (pintype "passive"))
    )
    (net (code "104") (name "unconnected-(U1-(CLKO{slash}ICP3{slash}INT7)_PE7-Pad9)") (class "Default")
      (node (ref "U1") (pin "9") (pinfunction "(CLKO/ICP3/INT7)_PE7_9") (pintype "bidirectional"))
    )
    (net (code "105") (name "unconnected-(U1-(ICP1)_PD4-Pad47)") (class "Default")
      (node (ref "U1") (pin "47") (pinfunction "(ICP1)_PD4_47") (pintype "bidirectional"))
    )
    (net (code "106") (name "unconnected-(U1-(ICP4)_PL0-Pad35)") (class "Default")
      (node (ref "U1") (pin "35") (pinfunction "(ICP4)_PL0_35") (pintype "bidirectional"))
    )
    (net (code "107") (name "unconnected-(U1-(ICP5)_PL1-Pad36)") (class "Default")
      (node (ref "U1") (pin "36") (pinfunction "(ICP5)_PL1_36") (pintype "bidirectional"))
    )
    (net (code "108") (name "unconnected-(U1-(OC1B{slash}PCINT6)_PB6-Pad25)") (class "Default")
      (node (ref "U1") (pin "25") (pinfunction "(OC1B/PCINT6)_PB6_25") (pintype "bidirectional"))
    )
    (net (code "109") (name "unconnected-(U1-(OC5A)_PL3-Pad38)") (class "Default")
      (node (ref "U1") (pin "38") (pinfunction "(OC5A)_PL3_38") (pintype "bidirectional"))
    )
    (net (code "110") (name "unconnected-(U1-(OC5B)_PL4-Pad39)") (class "Default")
      (node (ref "U1") (pin "39") (pinfunction "(OC5B)_PL4_39") (pintype "bidirectional"))
    )
    (net (code "111") (name "unconnected-(U1-(RXD1{slash}INT2)_PD2-Pad45)") (class "Default")
      (node (ref "U1") (pin "45") (pinfunction "(RXD1/INT2)_PD2_45") (pintype "bidirectional"))
    )
    (net (code "112") (name "unconnected-(U1-(RXD2)_PH0-Pad12)") (class "Default")
      (node (ref "U1") (pin "12") (pinfunction "(RXD2)_PH0_12") (pintype "bidirectional"))
    )
    (net (code "113") (name "unconnected-(U1-(T0)_PD7-Pad50)") (class "Default")
      (node (ref "U1") (pin "50") (pinfunction "(T0)_PD7_50") (pintype "bidirectional"))
    )
    (net (code "114") (name "unconnected-(U1-(T1)_PD6-Pad49)") (class "Default")
      (node (ref "U1") (pin "49") (pinfunction "(T1)_PD6_49") (pintype "bidirectional"))
    )
    (net (code "115") (name "unconnected-(U1-(T3{slash}INT6)_PE6-Pad8)") (class "Default")
      (node (ref "U1") (pin "8") (pinfunction "(T3/INT6)_PE6_8") (pintype "bidirectional"))
    )
    (net (code "116") (name "unconnected-(U1-(T4)_PH7-Pad27)") (class "Default")
      (node (ref "U1") (pin "27") (pinfunction "(T4)_PH7_27") (pintype "bidirectional"))
    )
    (net (code "117") (name "unconnected-(U1-(T5)_PL2-Pad37)") (class "Default")
      (node (ref "U1") (pin "37") (pinfunction "(T5)_PL2_37") (pintype "bidirectional"))
    )
    (net (code "118") (name "unconnected-(U1-(TOSC1)_PG4-Pad29)") (class "Default")
      (node (ref "U1") (pin "29") (pinfunction "(TOSC1)_PG4_29") (pintype "bidirectional"))
    )
    (net (code "119") (name "unconnected-(U1-(TOSC2)_PG3-Pad28)") (class "Default")
      (node (ref "U1") (pin "28") (pinfunction "(TOSC2)_PG3_28") (pintype "bidirectional"))
    )
    (net (code "120") (name "unconnected-(U1-(TXD1{slash}INT3)_PD3-Pad46)") (class "Default")
      (node (ref "U1") (pin "46") (pinfunction "(TXD1/INT3)_PD3_46") (pintype "bidirectional"))
    )
    (net (code "121") (name "unconnected-(U1-(TXD2)_PH1-Pad13)") (class "Default")
      (node (ref "U1") (pin "13") (pinfunction "(TXD2)_PH1_13") (pintype "bidirectional"))
    )
    (net (code "122") (name "unconnected-(U1-(XCK0{slash}AIN0)_PE2-Pad4)") (class "Default")
      (node (ref "U1") (pin "4") (pinfunction "(XCK0/AIN0)_PE2_4") (pintype "bidirectional"))
    )
    (net (code "123") (name "unconnected-(U1-(XCK1)_PD5-Pad48)") (class "Default")
      (node (ref "U1") (pin "48") (pinfunction "(XCK1)_PD5_48") (pintype "bidirectional"))
    )
    (net (code "124") (name "unconnected-(U1-(XCK2)_PH2-Pad14)") (class "Default")
      (node (ref "U1") (pin "14") (pinfunction "(XCK2)_PH2_14") (pintype "bidirectional"))
    )
    (net (code "125") (name "unconnected-(U1-AREF-Pad98)") (class "Default")
      (node (ref "U1") (pin "98") (pinfunction "AREF_98") (pintype "input"))
    )
    (net (code "126") (name "unconnected-(U1-OC5C)_PL5-Pad40)") (class "Default")
      (node (ref "U1") (pin "40") (pinfunction "OC5C)_PL5_40") (pintype "bidirectional"))
    )
    (net (code "127") (name "unconnected-(U1-PA0_(AD0)-Pad78)") (class "Default")
      (node (ref "U1") (pin "78") (pinfunction "PA0_(AD0)_78") (pintype "bidirectional"))
    )
    (net (code "128") (name "unconnected-(U1-PA1_(AD1)-Pad77)") (class "Default")
      (node (ref "U1") (pin "77") (pinfunction "PA1_(AD1)_77") (pintype "bidirectional"))
    )
    (net (code "129") (name "unconnected-(U1-PA2_(AD2)-Pad76)") (class "Default")
      (node (ref "U1") (pin "76") (pinfunction "PA2_(AD2)_76") (pintype "bidirectional"))
    )
    (net (code "130") (name "unconnected-(U1-PA3_(AD3)-Pad75)") (class "Default")
      (node (ref "U1") (pin "75") (pinfunction "PA3_(AD3)_75") (pintype "bidirectional"))
    )
    (net (code "131") (name "unconnected-(U1-PA4_(AD4)-Pad74)") (class "Default")
      (node (ref "U1") (pin "74") (pinfunction "PA4_(AD4)_74") (pintype "bidirectional"))
    )
    (net (code "132") (name "unconnected-(U1-PA5_(AD5)-Pad73)") (class "Default")
      (node (ref "U1") (pin "73") (pinfunction "PA5_(AD5)_73") (pintype "bidirectional"))
    )
    (net (code "133") (name "unconnected-(U1-PA6_(AD6)-Pad72)") (class "Default")
      (node (ref "U1") (pin "72") (pinfunction "PA6_(AD6)_72") (pintype "bidirectional"))
    )
    (net (code "134") (name "unconnected-(U1-PA7_(AD7)-Pad71)") (class "Default")
      (node (ref "U1") (pin "71") (pinfunction "PA7_(AD7)_71") (pintype "bidirectional"))
    )
    (net (code "135") (name "unconnected-(U1-PC0_(A8)-Pad53)") (class "Default")
      (node (ref "U1") (pin "53") (pinfunction "PC0_(A8)_53") (pintype "bidirectional"))
    )
    (net (code "136") (name "unconnected-(U1-PC1_(A9)-Pad54)") (class "Default")
      (node (ref "U1") (pin "54") (pinfunction "PC1_(A9)_54") (pintype "bidirectional"))
    )
    (net (code "137") (name "unconnected-(U1-PC2_(A10)-Pad55)") (class "Default")
      (node (ref "U1") (pin "55") (pinfunction "PC2_(A10)_55") (pintype "bidirectional"))
    )
    (net (code "138") (name "unconnected-(U1-PC3_(A11)-Pad56)") (class "Default")
      (node (ref "U1") (pin "56") (pinfunction "PC3_(A11)_56") (pintype "bidirectional"))
    )
    (net (code "139") (name "unconnected-(U1-PC4_(A12)-Pad57)") (class "Default")
      (node (ref "U1") (pin "57") (pinfunction "PC4_(A12)_57") (pintype "bidirectional"))
    )
    (net (code "140") (name "unconnected-(U1-PC5_(A13)-Pad58)") (class "Default")
      (node (ref "U1") (pin "58") (pinfunction "PC5_(A13)_58") (pintype "bidirectional"))
    )
    (net (code "141") (name "unconnected-(U1-PC6_(A14)-Pad59)") (class "Default")
      (node (ref "U1") (pin "59") (pinfunction "PC6_(A14)_59") (pintype "bidirectional"))
    )
    (net (code "142") (name "unconnected-(U1-PC7_(A15)-Pad60)") (class "Default")
      (node (ref "U1") (pin "60") (pinfunction "PC7_(A15)_60") (pintype "bidirectional"))
    )
    (net (code "143") (name "unconnected-(U1-PF4_(ADC4{slash}TCK)-Pad93)") (class "Default")
      (node (ref "U1") (pin "93") (pinfunction "PF4_(ADC4/TCK)_93") (pintype "bidirectional"))
    )
    (net (code "144") (name "unconnected-(U1-PF5_(ADC5{slash}TMS)-Pad92)") (class "Default")
      (node (ref "U1") (pin "92") (pinfunction "PF5_(ADC5/TMS)_92") (pintype "bidirectional"))
    )
    (net (code "145") (name "unconnected-(U1-PF6_(ADC6{slash}TDO)-Pad91)") (class "Default")
      (node (ref "U1") (pin "91") (pinfunction "PF6_(ADC6/TDO)_91") (pintype "bidirectional"))
    )
    (net (code "146") (name "unconnected-(U1-PF7_(ADC7{slash}TDI)-Pad90)") (class "Default")
      (node (ref "U1") (pin "90") (pinfunction "PF7_(ADC7/TDI)_90") (pintype "bidirectional"))
    )
    (net (code "147") (name "unconnected-(U1-PG1_(~{RD})-Pad52)") (class "Default")
      (node (ref "U1") (pin "52") (pinfunction "PG1_(~{RD})_52") (pintype "bidirectional"))
    )
    (net (code "148") (name "unconnected-(U1-PG2_(ALE)-Pad70)") (class "Default")
      (node (ref "U1") (pin "70") (pinfunction "PG2_(ALE)_70") (pintype "bidirectional"))
    )
    (net (code "149") (name "unconnected-(U1-PJ0_(RXD3{slash}PCINT9)-Pad63)") (class "Default")
      (node (ref "U1") (pin "63") (pinfunction "PJ0_(RXD3/PCINT9)_63") (pintype "bidirectional"))
    )
    (net (code "150") (name "unconnected-(U1-PJ1_(TXD3{slash}PCINT10)-Pad64)") (class "Default")
      (node (ref "U1") (pin "64") (pinfunction "PJ1_(TXD3/PCINT10)_64") (pintype "bidirectional"))
    )
    (net (code "151") (name "unconnected-(U1-PJ2_(XCK3{slash}PCINT11)-Pad65)") (class "Default")
      (node (ref "U1") (pin "65") (pinfunction "PJ2_(XCK3/PCINT11)_65") (pintype "bidirectional"))
    )
    (net (code "152") (name "unconnected-(U1-PJ3_(PCINT12)-Pad66)") (class "Default")
      (node (ref "U1") (pin "66") (pinfunction "PJ3_(PCINT12)_66") (pintype "bidirectional"))
    )
    (net (code "153") (name "unconnected-(U1-PJ4_(PCINT13)-Pad67)") (class "Default")
      (node (ref "U1") (pin "67") (pinfunction "PJ4_(PCINT13)_67") (pintype "bidirectional"))
    )
    (net (code "154") (name "unconnected-(U1-PJ5_(PCINT14)-Pad68)") (class "Default")
      (node (ref "U1") (pin "68") (pinfunction "PJ5_(PCINT14)_68") (pintype "bidirectional"))
    )
    (net (code "155") (name "unconnected-(U1-PJ6_(PCINT15)-Pad69)") (class "Default")
      (node (ref "U1") (pin "69") (pinfunction "PJ6_(PCINT15)_69") (pintype "bidirectional"))
    )
    (net (code "156") (name "unconnected-(U1-PJ7-Pad79)") (class "Default")
      (node (ref "U1") (pin "79") (pinfunction "PJ7_79") (pintype "bidirectional"))
    )
    (net (code "157") (name "unconnected-(U1-PK0_(ADC8{slash}PCINT16)-Pad89)") (class "Default")
      (node (ref "U1") (pin "89") (pinfunction "PK0_(ADC8/PCINT16)_89") (pintype "bidirectional"))
    )
    (net (code "158") (name "unconnected-(U1-PK1_(ADC9{slash}PCINT17)-Pad88)") (class "Default")
      (node (ref "U1") (pin "88") (pinfunction "PK1_(ADC9/PCINT17)_88") (pintype "bidirectional"))
    )
    (net (code "159") (name "unconnected-(U1-PK2_(ADC10{slash}PCINT18)-Pad87)") (class "Default")
      (node (ref "U1") (pin "87") (pinfunction "PK2_(ADC10/PCINT18)_87") (pintype "bidirectional"))
    )
    (net (code "160") (name "unconnected-(U1-PK3_(ADC11{slash}PCINT19)-Pad86)") (class "Default")
      (node (ref "U1") (pin "86") (pinfunction "PK3_(ADC11/PCINT19)_86") (pintype "bidirectional"))
    )
    (net (code "161") (name "unconnected-(U1-PK4_(ADC12{slash}PCINT20)-Pad85)") (class "Default")
      (node (ref "U1") (pin "85") (pinfunction "PK4_(ADC12/PCINT20)_85") (pintype "bidirectional"))
    )
    (net (code "162") (name "unconnected-(U1-PK5_(ADC13{slash}PCINT21)-Pad84)") (class "Default")
      (node (ref "U1") (pin "84") (pinfunction "PK5_(ADC13/PCINT21)_84") (pintype "bidirectional"))
    )
    (net (code "163") (name "unconnected-(U1-PK6_(ADC14{slash}PCINT22)-Pad83)") (class "Default")
      (node (ref "U1") (pin "83") (pinfunction "PK6_(ADC14/PCINT22)_83") (pintype "bidirectional"))
    )
    (net (code "164") (name "unconnected-(U1-PL6-Pad41)") (class "Default")
      (node (ref "U1") (pin "41") (pinfunction "PL6_41") (pintype "bidirectional"))
    )
    (net (code "165") (name "unconnected-(U1-PL7-Pad42)") (class "Default")
      (node (ref "U1") (pin "42") (pinfunction "PL7_42") (pintype "bidirectional"))
    )
    (net (code "166") (name "unconnected-(U2-CHR0-Pad15)") (class "Default")
      (node (ref "U2") (pin "15") (pinfunction "CHR0_15") (pintype "output"))
    )
    (net (code "167") (name "unconnected-(U2-CHR1-Pad14)") (class "Default")
      (node (ref "U2") (pin "14") (pinfunction "CHR1_14") (pintype "output"))
    )
    (net (code "168") (name "unconnected-(U2-CHREN-Pad13)") (class "Default")
      (node (ref "U2") (pin "13") (pinfunction "CHREN_13") (pintype "output"))
    )
    (net (code "169") (name "unconnected-(U2-CTS-Pad23)") (class "Default")
      (node (ref "U2") (pin "23") (pinfunction "CTS_23") (pintype "input"))
    )
    (net (code "170") (name "unconnected-(U2-DCD-Pad1)") (class "Default")
      (node (ref "U2") (pin "1") (pinfunction "DCD_1") (pintype "input"))
    )
    (net (code "171") (name "unconnected-(U2-DSR-Pad27)") (class "Default")
      (node (ref "U2") (pin "27") (pinfunction "DSR_27") (pintype "input"))
    )
    (net (code "172") (name "unconnected-(U2-GPIO.2{slash}RS485-Pad17)") (class "Default")
      (node (ref "U2") (pin "17") (pinfunction "GPIO.2/RS485_17") (pintype "bidirectional"))
    )
    (net (code "173") (name "unconnected-(U2-GPIO.3{slash}WAKEUP-Pad16)") (class "Default")
      (node (ref "U2") (pin "16") (pinfunction "GPIO.3/WAKEUP_16") (pintype "bidirectional"))
    )
    (net (code "174") (name "unconnected-(U2-GPIO.4-Pad22)") (class "Default")
      (node (ref "U2") (pin "22") (pinfunction "GPIO.4_22") (pintype "bidirectional"))
    )
    (net (code "175") (name "unconnected-(U2-GPIO.5-Pad21)") (class "Default")
      (node (ref "U2") (pin "21") (pinfunction "GPIO.5_21") (pintype "bidirectional"))
    )
    (net (code "176") (name "unconnected-(U2-GPIO.6-Pad20)") (class "Default")
      (node (ref "U2") (pin "20") (pinfunction "GPIO.6_20") (pintype "bidirectional"))
    )
    (net (code "177") (name "unconnected-(U2-RI{slash}CLK-Pad2)") (class "Default")
      (node (ref "U2") (pin "2") (pinfunction "RI/CLK_2") (pintype "bidirectional"))
    )
    (net (code "178") (name "unconnected-(U2-RTS-Pad24)") (class "Default")
      (node (ref "U2") (pin "24") (pinfunction "RTS_24") (pintype "output"))
    )
    (net (code "179") (name "unconnected-(U2-SUSPEND-Pad12)") (class "Default")
      (node (ref "U2") (pin "12") (pinfunction "SUSPEND_12") (pintype "output"))
    )
    (net (code "180") (name "unconnected-(U2-~{SUSPENDB}-Pad11)") (class "Default")
      (node (ref "U2") (pin "11") (pinfunction "~{SUSPENDB}_11") (pintype "output"))
    )
    (net (code "181") (name "unconnected-(U4-PG-PadP$7)") (class "Default")
      (node (ref "U4") (pin "P$7") (pinfunction "PG_P$7") (pintype "bidirectional"))
    )
    (net (code "182") (name "unconnected-(U5-NC-1-Pad3)") (class "Default")
      (node (ref "U5") (pin "3") (pinfunction "NC-1_3") (pintype "bidirectional"))
    )
    (net (code "183") (name "unconnected-(U5-NC-Pad5)") (class "Default")
      (node (ref "U5") (pin "5") (pinfunction "NC_5") (pintype "bidirectional"))
    )
    (net (code "184") (name "unconnected-(U8-VREF-Pad5)") (class "Default")
      (node (ref "U8") (pin "5") (pinfunction "VREF_5") (pintype "passive"))
    )
    (net (code "185") (name "unconnected-(U9-CLKOUT{slash}SOF-Pad3)") (class "Default")
      (node (ref "U9") (pin "3") (pinfunction "CLKOUT/SOF_3") (pintype "output"))
    )
    (net (code "186") (name "unconnected-(U9-~{INT}-Pad12)") (class "Default")
      (node (ref "U9") (pin "12") (pinfunction "~{INT}_12") (pintype "output"))
    )
    (net (code "187") (name "unconnected-(U9-~{RX0BF}-Pad11)") (class "Default")
      (node (ref "U9") (pin "11") (pinfunction "~{RX0BF}_11") (pintype "output"))
    )
    (net (code "188") (name "unconnected-(U9-~{RX1BF}-Pad10)") (class "Default")
      (node (ref "U9") (pin "10") (pinfunction "~{RX1BF}_10") (pintype "output"))
    )
    (net (code "189") (name "unconnected-(U9-~{TX0RTS}-Pad4)") (class "Default")
      (node (ref "U9") (pin "4") (pinfunction "~{TX0RTS}_4") (pintype "input"))
    )
    (net (code "190") (name "unconnected-(U9-~{TX1RTS}-Pad5)") (class "Default")
      (node (ref "U9") (pin "5") (pinfunction "~{TX1RTS}_5") (pintype "input"))
    )
    (net (code "191") (name "unconnected-(U9-~{TX2RTS}-Pad6)") (class "Default")
      (node (ref "U9") (pin "6") (pinfunction "~{TX2RTS}_6") (pintype "input"))
    )
  )
)
